# 1_Main__schdoc.net
KiCad netlist of a schematic drawn in Altium Designer
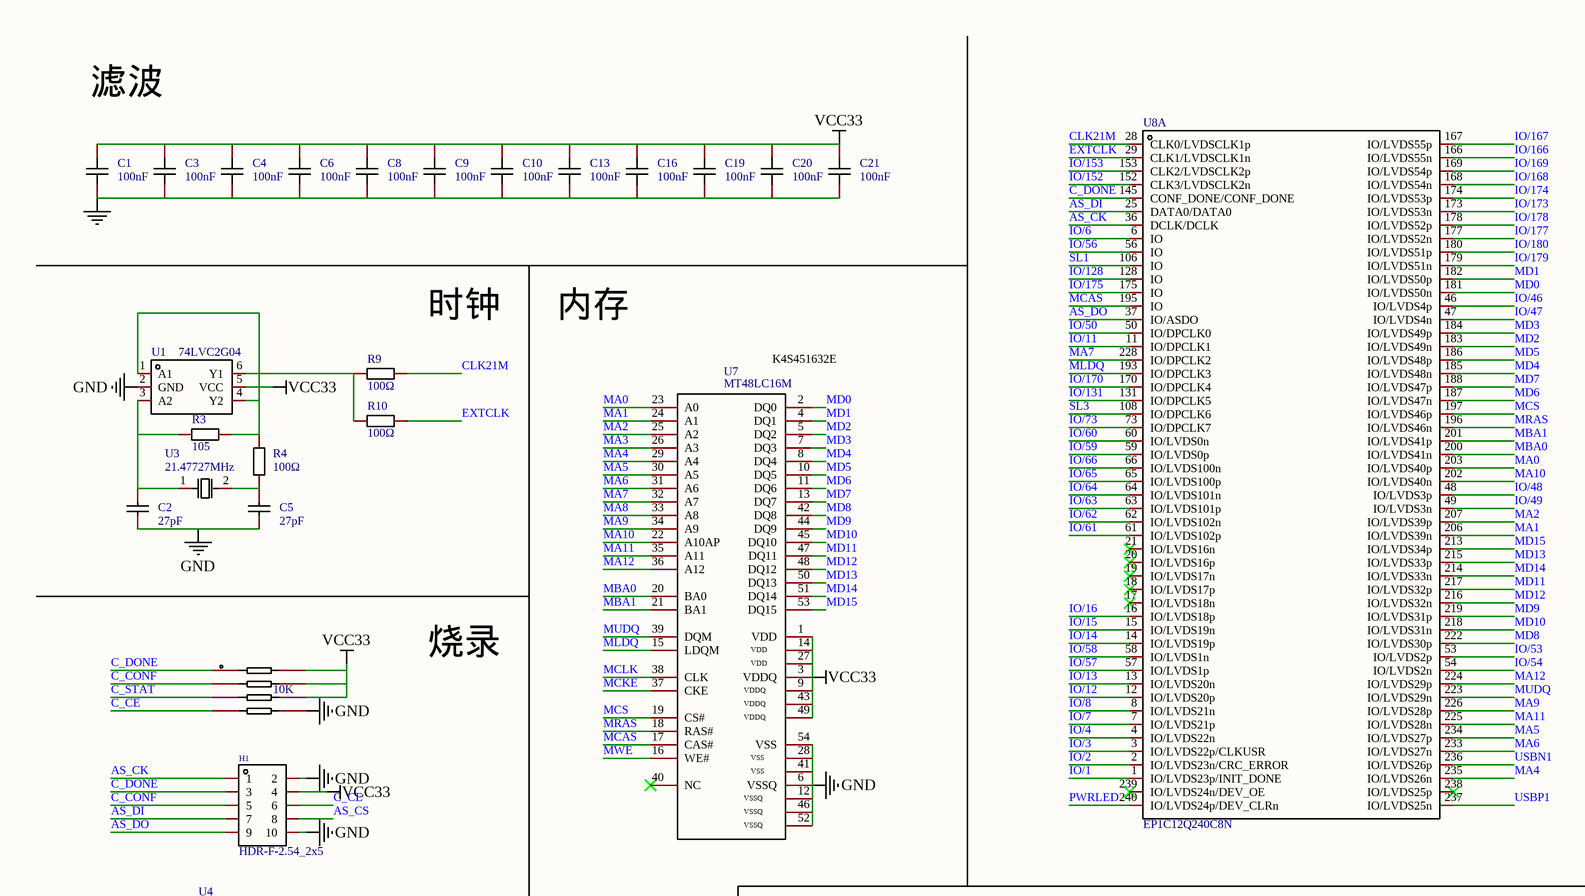
[diagram p0: 1_Main_核心板.schdoc.schdoc, top left]
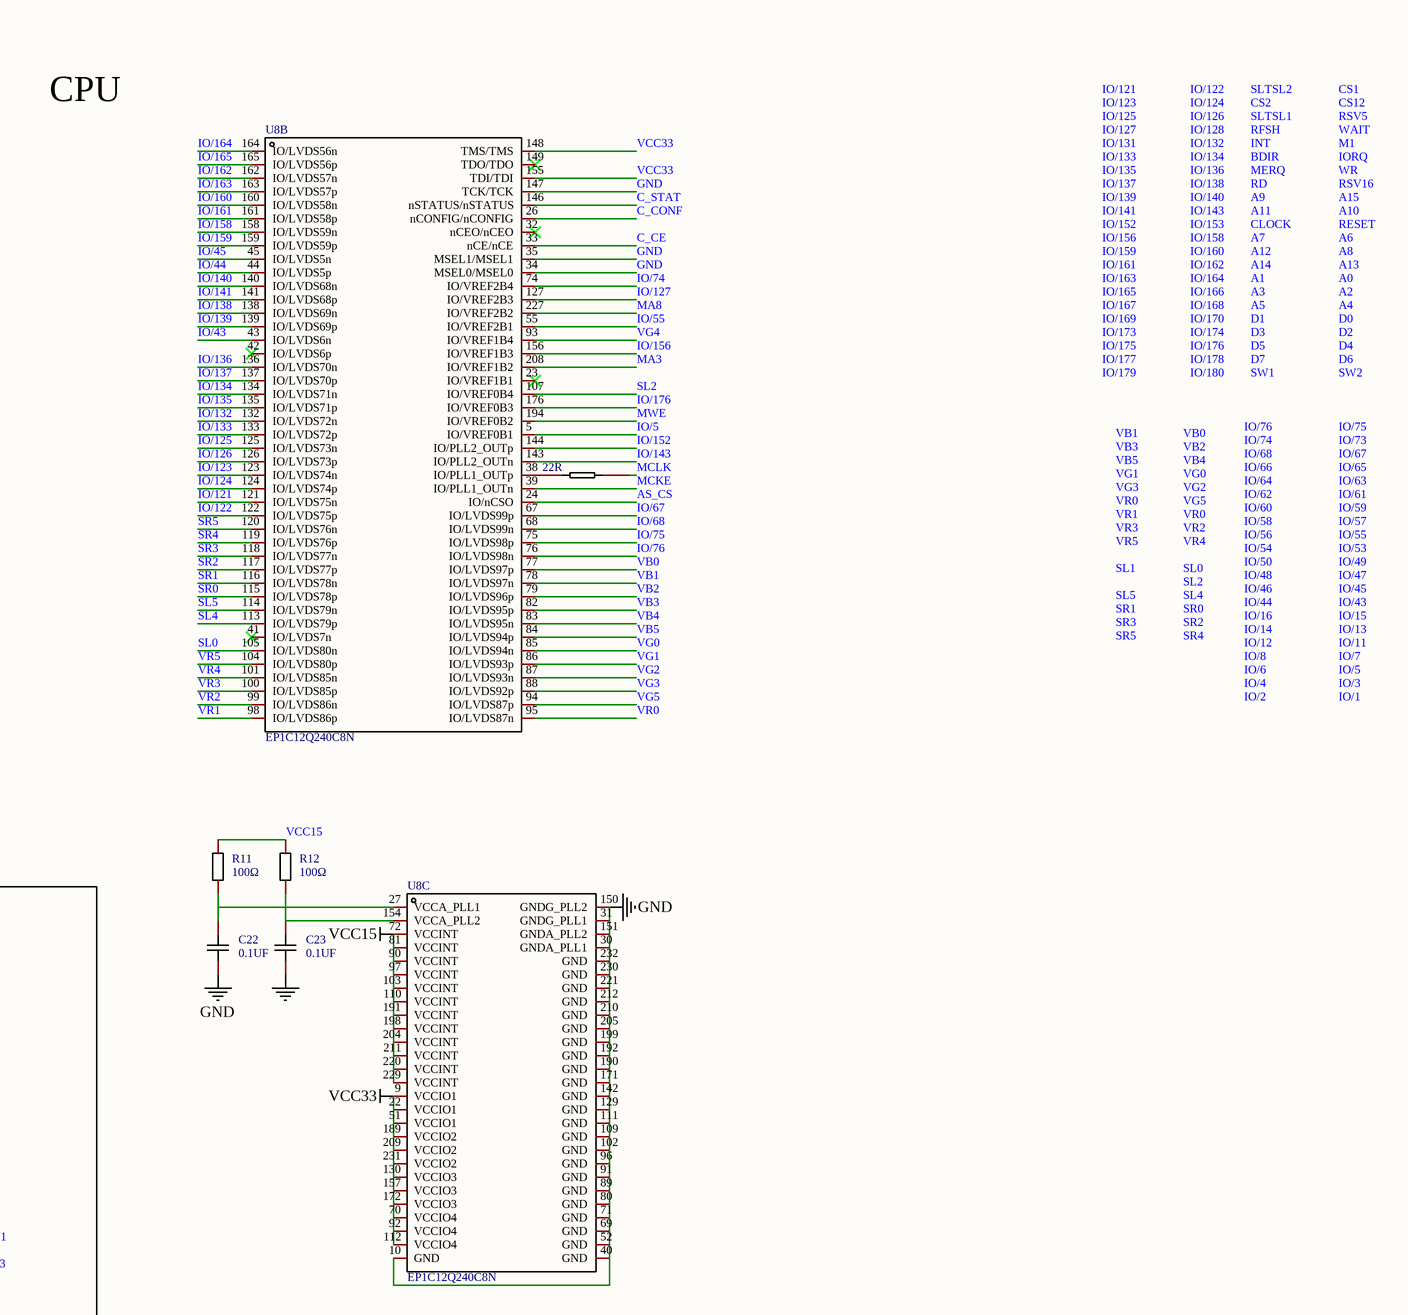
[diagram p1: 1_Main_核心板.schdoc.schdoc, top right]
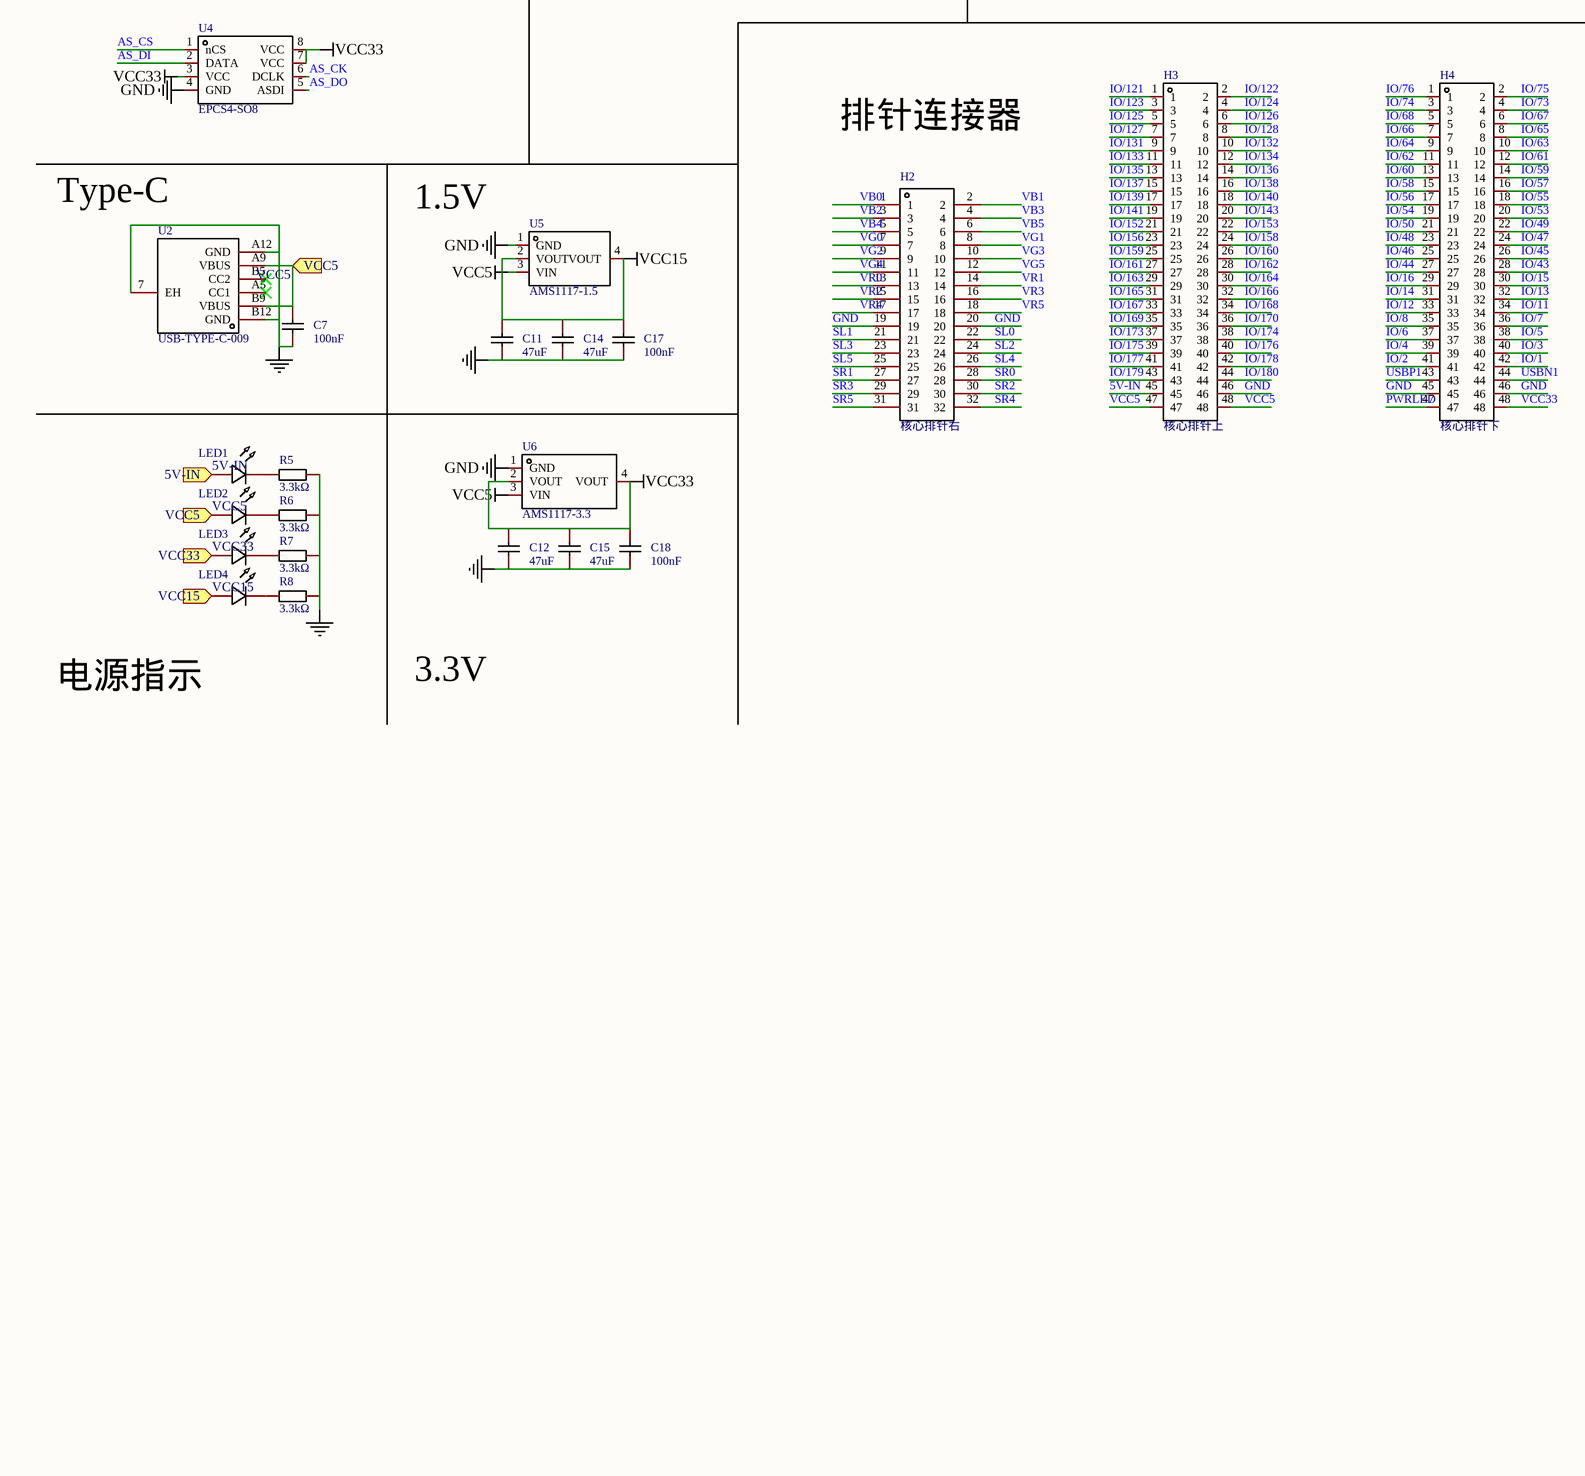
[diagram p2: 1_Main_核心板.schdoc.schdoc, bottom left]

(export (version "E")
  (design (tool "Eeschema 10.0.6"))
  (components
    (comp (ref "C1")
      (value "100nF")
      (fields
        (field (name "NAME") "100nF")
        (field (name "MANUFACTURER") "YAGEO(国巨)")
        (field (name "MANUFACTURER PART") "CC0603KRX7R9BB104")
        (field (name "TOLERANCE") "±10%")
      )
      (libsource (lib "altium-import") (part "root_1_CC0603KRX7R9BB104_"))
    )
    (comp (ref "C2")
      (value "27pF")
      (fields
        (field (name "NAME") "27pF")
        (field (name "MANUFACTURER") "YAGEO(国巨)")
        (field (name "MANUFACTURER PART") "CC0603JRNPO9BN270")
        (field (name "TOLERANCE") "±5%")
      )
      (libsource (lib "altium-import") (part "root_1_CC0603JRNPO9BN270_"))
    )
    (comp (ref "C3")
      (value "100nF")
      (fields
        (field (name "NAME") "100nF")
        (field (name "MANUFACTURER") "YAGEO(国巨)")
        (field (name "MANUFACTURER PART") "CC0603KRX7R9BB104")
        (field (name "TOLERANCE") "±10%")
      )
      (libsource (lib "altium-import") (part "root_1_CC0603KRX7R9BB104_"))
    )
    (comp (ref "C4")
      (value "100nF")
      (fields
        (field (name "NAME") "100nF")
        (field (name "MANUFACTURER") "YAGEO(国巨)")
        (field (name "MANUFACTURER PART") "CC0603KRX7R9BB104")
        (field (name "TOLERANCE") "±10%")
      )
      (libsource (lib "altium-import") (part "root_1_CC0603KRX7R9BB104_"))
    )
    (comp (ref "C5")
      (value "27pF")
      (fields
        (field (name "NAME") "27pF")
        (field (name "MANUFACTURER") "YAGEO(国巨)")
        (field (name "MANUFACTURER PART") "CC0603JRNPO9BN270")
        (field (name "TOLERANCE") "±5%")
      )
      (libsource (lib "altium-import") (part "root_1_CC0603JRNPO9BN270_"))
    )
    (comp (ref "C6")
      (value "100nF")
      (fields
        (field (name "NAME") "100nF")
        (field (name "MANUFACTURER") "YAGEO(国巨)")
        (field (name "MANUFACTURER PART") "CC0603KRX7R9BB104")
        (field (name "TOLERANCE") "±10%")
      )
      (libsource (lib "altium-import") (part "root_1_CC0603KRX7R9BB104_"))
    )
    (comp (ref "C7")
      (value "100nF")
      (fields
        (field (name "NAME") "100nF")
        (field (name "MANUFACTURER") "FH(风华)")
        (field (name "MANUFACTURER PART") "0603B104K500NT")
        (field (name "TOLERANCE") "±10%")
      )
      (libsource (lib "altium-import") (part "root_1_0603B104K500NT_"))
    )
    (comp (ref "C8")
      (value "100nF")
      (fields
        (field (name "NAME") "100nF")
        (field (name "MANUFACTURER") "YAGEO(国巨)")
        (field (name "MANUFACTURER PART") "CC0603KRX7R9BB104")
        (field (name "TOLERANCE") "±10%")
      )
      (libsource (lib "altium-import") (part "root_1_CC0603KRX7R9BB104_"))
    )
    (comp (ref "C9")
      (value "100nF")
      (fields
        (field (name "NAME") "100nF")
        (field (name "MANUFACTURER") "YAGEO(国巨)")
        (field (name "MANUFACTURER PART") "CC0603KRX7R9BB104")
        (field (name "TOLERANCE") "±10%")
      )
      (libsource (lib "altium-import") (part "root_1_CC0603KRX7R9BB104_"))
    )
    (comp (ref "C10")
      (value "100nF")
      (fields
        (field (name "NAME") "100nF")
        (field (name "MANUFACTURER") "YAGEO(国巨)")
        (field (name "MANUFACTURER PART") "CC0603KRX7R9BB104")
        (field (name "TOLERANCE") "±10%")
      )
      (libsource (lib "altium-import") (part "root_1_CC0603KRX7R9BB104_"))
    )
    (comp (ref "C11")
      (value "47uF")
      (fields
        (field (name "NAME") "47uF")
        (field (name "MANUFACTURER") "SAMSUNG(三星)")
        (field (name "MANUFACTURER PART") "CL21A476MQYNNNE")
        (field (name "TOLERANCE") "±20%")
      )
      (libsource (lib "altium-import") (part "root_1_CL21A476MQYNNNE_"))
    )
    (comp (ref "C12")
      (value "47uF")
      (fields
        (field (name "NAME") "47uF")
        (field (name "MANUFACTURER") "SAMSUNG(三星)")
        (field (name "MANUFACTURER PART") "CL21A476MQYNNNE")
        (field (name "TOLERANCE") "±20%")
      )
      (libsource (lib "altium-import") (part "root_1_CL21A476MQYNNNE_"))
    )
    (comp (ref "C13")
      (value "100nF")
      (fields
        (field (name "NAME") "100nF")
        (field (name "MANUFACTURER") "YAGEO(国巨)")
        (field (name "MANUFACTURER PART") "CC0603KRX7R9BB104")
        (field (name "TOLERANCE") "±10%")
      )
      (libsource (lib "altium-import") (part "root_1_CC0603KRX7R9BB104_"))
    )
    (comp (ref "C14")
      (value "47uF")
      (fields
        (field (name "NAME") "47uF")
        (field (name "MANUFACTURER") "SAMSUNG(三星)")
        (field (name "MANUFACTURER PART") "CL21A476MQYNNNE")
        (field (name "TOLERANCE") "±20%")
      )
      (libsource (lib "altium-import") (part "root_1_CL21A476MQYNNNE_"))
    )
    (comp (ref "C15")
      (value "47uF")
      (fields
        (field (name "NAME") "47uF")
        (field (name "MANUFACTURER") "SAMSUNG(三星)")
        (field (name "MANUFACTURER PART") "CL21A476MQYNNNE")
        (field (name "TOLERANCE") "±20%")
      )
      (libsource (lib "altium-import") (part "root_1_CL21A476MQYNNNE_"))
    )
    (comp (ref "C16")
      (value "100nF")
      (fields
        (field (name "NAME") "100nF")
        (field (name "MANUFACTURER") "YAGEO(国巨)")
        (field (name "MANUFACTURER PART") "CC0603KRX7R9BB104")
        (field (name "TOLERANCE") "±10%")
      )
      (libsource (lib "altium-import") (part "root_1_CC0603KRX7R9BB104_"))
    )
    (comp (ref "C17")
      (value "100nF")
      (fields
        (field (name "NAME") "100nF")
        (field (name "MANUFACTURER") "FH(风华)")
        (field (name "MANUFACTURER PART") "0603B104K500NT")
        (field (name "TOLERANCE") "±10%")
      )
      (libsource (lib "altium-import") (part "root_1_0603B104K500NT_"))
    )
    (comp (ref "C18")
      (value "100nF")
      (fields
        (field (name "NAME") "100nF")
        (field (name "MANUFACTURER") "FH(风华)")
        (field (name "MANUFACTURER PART") "0603B104K500NT")
        (field (name "TOLERANCE") "±10%")
      )
      (libsource (lib "altium-import") (part "root_1_0603B104K500NT_"))
    )
    (comp (ref "C19")
      (value "100nF")
      (fields
        (field (name "NAME") "100nF")
        (field (name "MANUFACTURER") "YAGEO(国巨)")
        (field (name "MANUFACTURER PART") "CC0603KRX7R9BB104")
        (field (name "TOLERANCE") "±10%")
      )
      (libsource (lib "altium-import") (part "root_1_CC0603KRX7R9BB104_"))
    )
    (comp (ref "C20")
      (value "100nF")
      (fields
        (field (name "NAME") "100nF")
        (field (name "MANUFACTURER") "YAGEO(国巨)")
        (field (name "MANUFACTURER PART") "CC0603KRX7R9BB104")
        (field (name "TOLERANCE") "±10%")
      )
      (libsource (lib "altium-import") (part "root_1_CC0603KRX7R9BB104_"))
    )
    (comp (ref "C21")
      (value "100nF")
      (fields
        (field (name "NAME") "100nF")
        (field (name "MANUFACTURER") "YAGEO(国巨)")
        (field (name "MANUFACTURER PART") "CC0603KRX7R9BB104")
        (field (name "TOLERANCE") "±10%")
      )
      (libsource (lib "altium-import") (part "root_1_CC0603KRX7R9BB104_"))
    )
    (comp (ref "C22")
      (value "0.1UF")
      (fields (field (name "NAME") "0.1UF"))
      (libsource (lib "altium-import") (part "root_3_0.1UF_"))
    )
    (comp (ref "C23")
      (value "0.1UF")
      (fields (field (name "NAME") "0.1UF"))
      (libsource (lib "altium-import") (part "root_3_mirrored_0.1UF_"))
    )
    (comp (ref "H1")
      (value "HDR-F-2.54_2x5")
      (description "排数:双排;总孔位数:10P;间距:2.54mm;行距:2.54mm;安装类型:直插;塑高:-;触头材质:黄铜;触头镀层:-;")
      (fields (field (name "NAME") "HDR-F-2.54_2x5") (field (name "MANUFACTURER") "BOOMELE(博穆精密)"))
      (libsource (lib "altium-import") (part "root_0_排母2.54mm2*5p 直_"))
    )
    (comp (ref "H2")
      (value "核心排针右")
      (fields (field (name "NAME") "核心排针右") (field (name "MANUFACTURER") "Ckmtw(灿科盟)"))
      (libsource (lib "altium-import") (part "root_0_B-2100S32P-B110_"))
    )
    (comp (ref "H3")
      (value "核心排针上")
      (fields (field (name "NAME") "核心排针上") (field (name "MANUFACTURER") "XKB Connectivity(中国星坤)"))
      (libsource (lib "altium-import") (part "root_0_X6521WV-2x24H-C60D30_"))
    )
    (comp (ref "H4")
      (value "核心排针下")
      (fields (field (name "NAME") "核心排针下") (field (name "MANUFACTURER") "XKB Connectivity(中国星坤)"))
      (libsource (lib "altium-import") (part "root_0_X6521WV-2x24H-C60D30_"))
    )
    (comp (ref "LED1") (value "LED_0603-R") (libsource (lib "altium-import") (part "root_0_LED_0603-R_")))
    (comp (ref "LED2") (value "LED_0603-R") (libsource (lib "altium-import") (part "root_0_LED_0603-R_")))
    (comp (ref "LED3") (value "LED_0603-R") (libsource (lib "altium-import") (part "root_0_LED_0603-R_")))
    (comp (ref "LED4") (value "LED_0603-R") (libsource (lib "altium-import") (part "root_0_LED_0603-R_")))
    (comp (ref "R3")
      (value "105")
      (fields
        (field (name "NAME") "105")
        (field (name "MANUFACTURER") "UNI-ROYAL(厚声)")
        (field (name "MANUFACTURER PART") "0603WAF1004T5E")
        (field (name "TOLERANCE") "±1%")
      )
      (libsource (lib "altium-import") (part "root_0_0603WAF1004T5E_"))
    )
    (comp (ref "R4")
      (value "100Ω")
      (fields
        (field (name "NAME") "100Ω")
        (field (name "MANUFACTURER") "UNI-ROYAL(厚声)")
        (field (name "MANUFACTURER PART") "0603WAF1000T5E")
        (field (name "TOLERANCE") "±1%")
      )
      (libsource (lib "altium-import") (part "root_1_0603WAF1000T5E_"))
    )
    (comp (ref "R5")
      (value "3.3kΩ")
      (fields
        (field (name "NAME") "3.3kΩ")
        (field (name "MANUFACTURER") "UNI-ROYAL(厚声)")
        (field (name "MANUFACTURER PART") "0603WAF3301T5E")
        (field (name "TOLERANCE") "±1%")
      )
      (libsource (lib "altium-import") (part "root_0_0603WAF3301T5E_"))
    )
    (comp (ref "R6")
      (value "3.3kΩ")
      (fields
        (field (name "NAME") "3.3kΩ")
        (field (name "MANUFACTURER") "UNI-ROYAL(厚声)")
        (field (name "MANUFACTURER PART") "0603WAF3301T5E")
        (field (name "TOLERANCE") "±1%")
      )
      (libsource (lib "altium-import") (part "root_0_0603WAF3301T5E_"))
    )
    (comp (ref "R7")
      (value "3.3kΩ")
      (fields
        (field (name "NAME") "3.3kΩ")
        (field (name "MANUFACTURER") "UNI-ROYAL(厚声)")
        (field (name "MANUFACTURER PART") "0603WAF3301T5E")
        (field (name "TOLERANCE") "±1%")
      )
      (libsource (lib "altium-import") (part "root_0_0603WAF3301T5E_"))
    )
    (comp (ref "R8")
      (value "3.3kΩ")
      (fields
        (field (name "NAME") "3.3kΩ")
        (field (name "MANUFACTURER") "UNI-ROYAL(厚声)")
        (field (name "MANUFACTURER PART") "0603WAF3301T5E")
        (field (name "TOLERANCE") "±1%")
      )
      (libsource (lib "altium-import") (part "root_0_0603WAF3301T5E_"))
    )
    (comp (ref "R9")
      (value "100Ω")
      (fields
        (field (name "NAME") "100Ω")
        (field (name "MANUFACTURER") "UNI-ROYAL(厚声)")
        (field (name "MANUFACTURER PART") "0603WAF1000T5E")
        (field (name "TOLERANCE") "±1%")
      )
      (libsource (lib "altium-import") (part "root_0_0603WAF1000T5E_"))
    )
    (comp (ref "R10")
      (value "100Ω")
      (fields
        (field (name "NAME") "100Ω")
        (field (name "MANUFACTURER") "UNI-ROYAL(厚声)")
        (field (name "MANUFACTURER PART") "0603WAF1000T5E")
        (field (name "TOLERANCE") "±1%")
      )
      (libsource (lib "altium-import") (part "root_0_0603WAF1000T5E_"))
    )
    (comp (ref "R11")
      (value "100Ω")
      (fields
        (field (name "NAME") "100Ω")
        (field (name "MANUFACTURER") "UNI-ROYAL(厚声)")
        (field (name "MANUFACTURER PART") "0603WAF1000T5E")
        (field (name "TOLERANCE") "±1%")
      )
      (libsource (lib "altium-import") (part "root_1_0603WAF1000T5E_"))
    )
    (comp (ref "R12")
      (value "100Ω")
      (fields
        (field (name "NAME") "100Ω")
        (field (name "MANUFACTURER") "UNI-ROYAL(厚声)")
        (field (name "MANUFACTURER PART") "0603WAF1000T5E")
        (field (name "TOLERANCE") "±1%")
      )
      (libsource (lib "altium-import") (part "root_1_0603WAF1000T5E_"))
    )
    (comp (ref "R13")
      (value "22R")
      (fields (field (name "NAME") "22R"))
      (libsource (lib "altium-import") (part "root_0_Res_0603_"))
    )
    (comp (ref "RN2")
      (value "10K")
      (fields
        (field (name "NAME") "10K")
        (field (name "MANUFACTURER") "UNI-ROYAL(厚声)")
        (field (name "MANUFACTURER PART") "4D03WGJ0101T5E")
        (field (name "TOLERANCE") "±5%")
      )
      (libsource (lib "altium-import") (part "root_0_4D03WGJ0101T5E_"))
    )
    (comp (ref "U1")
      (value "74LVC2G04")
      (description "输入类型:-;通道数:2;电源电压:1.8V~5.5V;电源电流(最大值):1uA;灌电流(IOL):8mA;拉电流(IOH):8mA;最大传播延迟(tpd):5.6ns@5V,50pF;")
      (fields (field (name "NAME") "74LVC2G04") (field (name "MANUFACTURER") "onsemi(安森美)"))
      (libsource (lib "altium-import") (part "root_0_NC7WZU04P6X_"))
    )
    (comp (ref "U2")
      (value "USB-TYPE-C-009")
      (description "连接器类型:Type-C;标准:-;公母:母座;触点数量:6;端口数量:1;安装方式:卧贴;额定电流 - 电源:5A;工作温度范围:-25℃~+85℃;")
      (fields (field (name "NAME") "USB-TYPE-C-009") (field (name "MANUFACTURER") "DEALON(德艺隆)"))
      (libsource (lib "altium-import") (part "root_2_USB-TYPE-C-009_"))
    )
    (comp (ref "U3")
      (value "21.47727MHz")
      (description "频率:21.47727MHz;频率公差:±30ppm;频率稳定度:±50ppm;负载电容:-;")
      (fields
        (field (name "NAME") "21.47727MHz")
        (field (name "MANUFACTURER") "ECS")
        (field (name "MANUFACTURER PART") "ECS-214.7-S-4")
      )
      (libsource (lib "altium-import") (part "root_0_ECS-214.7-S-4_"))
    )
    (comp (ref "U4")
      (value "EPCS4-SO8")
      (fields (field (name "NAME") "EPCS4-SO8"))
      (libsource (lib "altium-import") (part "root_0_EPCS4-SO8_"))
    )
    (comp (ref "U5")
      (value "AMS1117-1.5")
      (description "输出类型:-;")
      (fields (field (name "NAME") "AMS1117-1.5") (field (name "MANUFACTURER") "JSMSEMI(杰盛微)"))
      (libsource (lib "altium-import") (part "root_0_AMS1117-1.5_C963403_"))
    )
    (comp (ref "U6")
      (value "AMS1117-3.3")
      (description "输出类型:固定;输出极性:正;最大输入电压:-;输出电压:3.3V;输出电流:1A;电源纹波抑制比(PSRR):72dB@(120Hz);")
      (fields (field (name "NAME") "AMS1117-3.3") (field (name "MANUFACTURER") "AMS"))
      (libsource (lib "altium-import") (part "root_0_AMS1117-3.3_C6186_"))
    )
    (comp (ref "U7")
      (value "MT48LC16M")
      (fields (field (name "NAME") "MT48LC16M"))
      (libsource (lib "altium-import") (part "root_0_MT48LC16M_"))
    )
    (comp (ref "U8")
      (value "EP1C12Q240C8N")
      (fields (field (name "NAME") "EP1C12Q240C8N") (field (name "MANUFACTURER") "Intel/Altera"))
      (libsource (lib "altium-import") (part "root_0_EP1C12Q240C8N_"))
    )
  )
  (nets
    (net (code "1") (name "/5V-IN") (class "Default")
      (node (ref "H3") (pin "45") (pinfunction "45_45") (pintype "passive"))
      (node (ref "LED1") (pin "2") (pinfunction "A_2") (pintype "passive"))
    )
    (net (code "18") (name "/AS_CK") (class "Default")
      (node (ref "H1") (pin "1") (pinfunction "1_1") (pintype "passive"))
      (node (ref "U4") (pin "6") (pinfunction "DCLK_6") (pintype "passive"))
      (node (ref "U8") (pin "36") (pinfunction "DCLK/DCLK_36") (pintype "passive"))
    )
    (net (code "19") (name "/AS_CS") (class "Default")
      (node (ref "H1") (pin "8") (pinfunction "8_8") (pintype "passive"))
      (node (ref "U4") (pin "1") (pinfunction "nCS_1") (pintype "passive"))
      (node (ref "U8") (pin "24") (pinfunction "IO/nCSO_24") (pintype "passive"))
    )
    (net (code "20") (name "/AS_DI") (class "Default")
      (node (ref "H1") (pin "7") (pinfunction "7_7") (pintype "passive"))
      (node (ref "U4") (pin "2") (pinfunction "DATA_2") (pintype "passive"))
      (node (ref "U8") (pin "25") (pinfunction "DATA0/DATA0_25") (pintype "passive"))
    )
    (net (code "21") (name "/AS_DO") (class "Default")
      (node (ref "H1") (pin "9") (pinfunction "9_9") (pintype "passive"))
      (node (ref "U4") (pin "5") (pinfunction "ASDI_5") (pintype "passive"))
      (node (ref "U8") (pin "37") (pinfunction "IO/ASDO_37") (pintype "passive"))
    )
    (net (code "23") (name "/CLK21M") (class "Default")
      (node (ref "R9") (pin "2") (pinfunction "2_2") (pintype "passive"))
      (node (ref "U8") (pin "28") (pinfunction "CLK0/LVDSCLK1p_28") (pintype "passive"))
    )
    (net (code "28") (name "/C_CE") (class "Default")
      (node (ref "H1") (pin "6") (pinfunction "6_6") (pintype "passive"))
      (node (ref "RN2") (pin "4") (pinfunction "4_4") (pintype "passive"))
      (node (ref "U8") (pin "33") (pinfunction "nCE/nCE_33") (pintype "passive"))
    )
    (net (code "29") (name "/C_CONF") (class "Default")
      (node (ref "H1") (pin "5") (pinfunction "5_5") (pintype "passive"))
      (node (ref "RN2") (pin "2") (pinfunction "2_2") (pintype "passive"))
      (node (ref "U8") (pin "26") (pinfunction "nCONFIG/nCONFIG_26") (pintype "passive"))
    )
    (net (code "30") (name "/C_DONE") (class "Default")
      (node (ref "H1") (pin "3") (pinfunction "3_3") (pintype "passive"))
      (node (ref "RN2") (pin "1") (pinfunction "1_1") (pintype "passive"))
      (node (ref "U8") (pin "145") (pinfunction "CONF_DONE/CONF_DONE_145") (pintype "passive"))
    )
    (net (code "31") (name "/C_STAT") (class "Default")
      (node (ref "RN2") (pin "3") (pinfunction "3_3") (pintype "passive"))
      (node (ref "U8") (pin "146") (pinfunction "nSTATUS/nSTATUS_146") (pintype "passive"))
    )
    (net (code "40") (name "/EXTCLK") (class "Default")
      (node (ref "R10") (pin "2") (pinfunction "2_2") (pintype "passive"))
      (node (ref "U8") (pin "29") (pinfunction "CLK1/LVDSCLK1n_29") (pintype "passive"))
    )
    (net (code "43") (name "/IO{slash}1") (class "Default")
      (node (ref "H4") (pin "42") (pinfunction "42_42") (pintype "passive"))
      (node (ref "U8") (pin "1") (pinfunction "IO/LVDS23p/INIT_DONE_1") (pintype "passive"))
    )
    (net (code "44") (name "/IO{slash}2") (class "Default")
      (node (ref "H4") (pin "41") (pinfunction "41_41") (pintype "passive"))
      (node (ref "U8") (pin "2") (pinfunction "IO/LVDS23n/CRC_ERROR_2") (pintype "passive"))
    )
    (net (code "45") (name "/IO{slash}3") (class "Default")
      (node (ref "H4") (pin "40") (pinfunction "40_40") (pintype "passive"))
      (node (ref "U8") (pin "3") (pinfunction "IO/LVDS22p/CLKUSR_3") (pintype "passive"))
    )
    (net (code "46") (name "/IO{slash}4") (class "Default")
      (node (ref "H4") (pin "39") (pinfunction "39_39") (pintype "passive"))
      (node (ref "U8") (pin "4") (pinfunction "IO/LVDS22n_4") (pintype "passive"))
    )
    (net (code "47") (name "/IO{slash}5") (class "Default")
      (node (ref "H4") (pin "38") (pinfunction "38_38") (pintype "passive"))
      (node (ref "U8") (pin "5") (pinfunction "IO/VREF0B1_5") (pintype "passive"))
    )
    (net (code "48") (name "/IO{slash}6") (class "Default")
      (node (ref "H4") (pin "37") (pinfunction "37_37") (pintype "passive"))
      (node (ref "U8") (pin "6") (pinfunction "IO_6") (pintype "passive"))
    )
    (net (code "49") (name "/IO{slash}7") (class "Default")
      (node (ref "H4") (pin "36") (pinfunction "36_36") (pintype "passive"))
      (node (ref "U8") (pin "7") (pinfunction "IO/LVDS21p_7") (pintype "passive"))
    )
    (net (code "50") (name "/IO{slash}8") (class "Default")
      (node (ref "H4") (pin "35") (pinfunction "35_35") (pintype "passive"))
      (node (ref "U8") (pin "8") (pinfunction "IO/LVDS21n_8") (pintype "passive"))
    )
    (net (code "51") (name "/IO{slash}11") (class "Default")
      (node (ref "H4") (pin "34") (pinfunction "34_34") (pintype "passive"))
      (node (ref "U8") (pin "11") (pinfunction "IO/DPCLK1_11") (pintype "passive"))
    )
    (net (code "52") (name "/IO{slash}12") (class "Default")
      (node (ref "H4") (pin "33") (pinfunction "33_33") (pintype "passive"))
      (node (ref "U8") (pin "12") (pinfunction "IO/LVDS20p_12") (pintype "passive"))
    )
    (net (code "53") (name "/IO{slash}13") (class "Default")
      (node (ref "H4") (pin "32") (pinfunction "32_32") (pintype "passive"))
      (node (ref "U8") (pin "13") (pinfunction "IO/LVDS20n_13") (pintype "passive"))
    )
    (net (code "54") (name "/IO{slash}14") (class "Default")
      (node (ref "H4") (pin "31") (pinfunction "31_31") (pintype "passive"))
      (node (ref "U8") (pin "14") (pinfunction "IO/LVDS19p_14") (pintype "passive"))
    )
    (net (code "55") (name "/IO{slash}15") (class "Default")
      (node (ref "H4") (pin "30") (pinfunction "30_30") (pintype "passive"))
      (node (ref "U8") (pin "15") (pinfunction "IO/LVDS19n_15") (pintype "passive"))
    )
    (net (code "56") (name "/IO{slash}16") (class "Default")
      (node (ref "H4") (pin "29") (pinfunction "29_29") (pintype "passive"))
      (node (ref "U8") (pin "16") (pinfunction "IO/LVDS18p_16") (pintype "passive"))
    )
    (net (code "57") (name "/IO{slash}43") (class "Default")
      (node (ref "H4") (pin "28") (pinfunction "28_28") (pintype "passive"))
      (node (ref "U8") (pin "43") (pinfunction "IO/LVDS6n_43") (pintype "passive"))
    )
    (net (code "58") (name "/IO{slash}44") (class "Default")
      (node (ref "H4") (pin "27") (pinfunction "27_27") (pintype "passive"))
      (node (ref "U8") (pin "44") (pinfunction "IO/LVDS5p_44") (pintype "passive"))
    )
    (net (code "59") (name "/IO{slash}45") (class "Default")
      (node (ref "H4") (pin "26") (pinfunction "26_26") (pintype "passive"))
      (node (ref "U8") (pin "45") (pinfunction "IO/LVDS5n_45") (pintype "passive"))
    )
    (net (code "60") (name "/IO{slash}46") (class "Default")
      (node (ref "H4") (pin "25") (pinfunction "25_25") (pintype "passive"))
      (node (ref "U8") (pin "46") (pinfunction "IO/LVDS4p_46") (pintype "passive"))
    )
    (net (code "61") (name "/IO{slash}47") (class "Default")
      (node (ref "H4") (pin "24") (pinfunction "24_24") (pintype "passive"))
      (node (ref "U8") (pin "47") (pinfunction "IO/LVDS4n_47") (pintype "passive"))
    )
    (net (code "62") (name "/IO{slash}48") (class "Default")
      (node (ref "H4") (pin "23") (pinfunction "23_23") (pintype "passive"))
      (node (ref "U8") (pin "48") (pinfunction "IO/LVDS3p_48") (pintype "passive"))
    )
    (net (code "63") (name "/IO{slash}49") (class "Default")
      (node (ref "H4") (pin "22") (pinfunction "22_22") (pintype "passive"))
      (node (ref "U8") (pin "49") (pinfunction "IO/LVDS3n_49") (pintype "passive"))
    )
    (net (code "64") (name "/IO{slash}50") (class "Default")
      (node (ref "H4") (pin "21") (pinfunction "21_21") (pintype "passive"))
      (node (ref "U8") (pin "50") (pinfunction "IO/DPCLK0_50") (pintype "passive"))
    )
    (net (code "65") (name "/IO{slash}53") (class "Default")
      (node (ref "H4") (pin "20") (pinfunction "20_20") (pintype "passive"))
      (node (ref "U8") (pin "53") (pinfunction "IO/LVDS2p_53") (pintype "passive"))
    )
    (net (code "66") (name "/IO{slash}54") (class "Default")
      (node (ref "H4") (pin "19") (pinfunction "19_19") (pintype "passive"))
      (node (ref "U8") (pin "54") (pinfunction "IO/LVDS2n_54") (pintype "passive"))
    )
    (net (code "67") (name "/IO{slash}55") (class "Default")
      (node (ref "H4") (pin "18") (pinfunction "18_18") (pintype "passive"))
      (node (ref "U8") (pin "55") (pinfunction "IO/VREF2B1_55") (pintype "passive"))
    )
    (net (code "68") (name "/IO{slash}56") (class "Default")
      (node (ref "H4") (pin "17") (pinfunction "17_17") (pintype "passive"))
      (node (ref "U8") (pin "56") (pinfunction "IO_56") (pintype "passive"))
    )
    (net (code "69") (name "/IO{slash}57") (class "Default")
      (node (ref "H4") (pin "16") (pinfunction "16_16") (pintype "passive"))
      (node (ref "U8") (pin "57") (pinfunction "IO/LVDS1p_57") (pintype "passive"))
    )
    (net (code "70") (name "/IO{slash}58") (class "Default")
      (node (ref "H4") (pin "15") (pinfunction "15_15") (pintype "passive"))
      (node (ref "U8") (pin "58") (pinfunction "IO/LVDS1n_58") (pintype "passive"))
    )
    (net (code "71") (name "/IO{slash}59") (class "Default")
      (node (ref "H4") (pin "14") (pinfunction "14_14") (pintype "passive"))
      (node (ref "U8") (pin "59") (pinfunction "IO/LVDS0p_59") (pintype "passive"))
    )
    (net (code "72") (name "/IO{slash}60") (class "Default")
      (node (ref "H4") (pin "13") (pinfunction "13_13") (pintype "passive"))
      (node (ref "U8") (pin "60") (pinfunction "IO/LVDS0n_60") (pintype "passive"))
    )
    (net (code "73") (name "/IO{slash}61") (class "Default")
      (node (ref "H4") (pin "12") (pinfunction "12_12") (pintype "passive"))
      (node (ref "U8") (pin "61") (pinfunction "IO/LVDS102p_61") (pintype "passive"))
    )
    (net (code "74") (name "/IO{slash}62") (class "Default")
      (node (ref "H4") (pin "11") (pinfunction "11_11") (pintype "passive"))
      (node (ref "U8") (pin "62") (pinfunction "IO/LVDS102n_62") (pintype "passive"))
    )
    (net (code "75") (name "/IO{slash}63") (class "Default")
      (node (ref "H4") (pin "10") (pinfunction "10_10") (pintype "passive"))
      (node (ref "U8") (pin "63") (pinfunction "IO/LVDS101p_63") (pintype "passive"))
    )
    (net (code "76") (name "/IO{slash}64") (class "Default")
      (node (ref "H4") (pin "9") (pinfunction "9_9") (pintype "passive"))
      (node (ref "U8") (pin "64") (pinfunction "IO/LVDS101n_64") (pintype "passive"))
    )
    (net (code "77") (name "/IO{slash}65") (class "Default")
      (node (ref "H4") (pin "8") (pinfunction "8_8") (pintype "passive"))
      (node (ref "U8") (pin "65") (pinfunction "IO/LVDS100p_65") (pintype "passive"))
    )
    (net (code "78") (name "/IO{slash}66") (class "Default")
      (node (ref "H4") (pin "7") (pinfunction "7_7") (pintype "passive"))
      (node (ref "U8") (pin "66") (pinfunction "IO/LVDS100n_66") (pintype "passive"))
    )
    (net (code "79") (name "/IO{slash}67") (class "Default")
      (node (ref "H4") (pin "6") (pinfunction "6_6") (pintype "passive"))
      (node (ref "U8") (pin "67") (pinfunction "IO/LVDS99p_67") (pintype "passive"))
    )
    (net (code "80") (name "/IO{slash}68") (class "Default")
      (node (ref "H4") (pin "5") (pinfunction "5_5") (pintype "passive"))
      (node (ref "U8") (pin "68") (pinfunction "IO/LVDS99n_68") (pintype "passive"))
    )
    (net (code "81") (name "/IO{slash}73") (class "Default")
      (node (ref "H4") (pin "4") (pinfunction "4_4") (pintype "passive"))
      (node (ref "U8") (pin "73") (pinfunction "IO/DPCLK7_73") (pintype "passive"))
    )
    (net (code "82") (name "/IO{slash}74") (class "Default")
      (node (ref "H4") (pin "3") (pinfunction "3_3") (pintype "passive"))
      (node (ref "U8") (pin "74") (pinfunction "IO/VREF2B4_74") (pintype "passive"))
    )
    (net (code "83") (name "/IO{slash}75") (class "Default")
      (node (ref "H4") (pin "2") (pinfunction "2_2") (pintype "passive"))
      (node (ref "U8") (pin "75") (pinfunction "IO/LVDS98p_75") (pintype "passive"))
    )
    (net (code "84") (name "/IO{slash}76") (class "Default")
      (node (ref "H4") (pin "1") (pinfunction "1_1") (pintype "passive"))
      (node (ref "U8") (pin "76") (pinfunction "IO/LVDS98n_76") (pintype "passive"))
    )
    (net (code "85") (name "/IO{slash}121") (class "Default")
      (node (ref "H3") (pin "1") (pinfunction "1_1") (pintype "passive"))
      (node (ref "U8") (pin "121") (pinfunction "IO/LVDS75n_121") (pintype "passive"))
    )
    (net (code "86") (name "/IO{slash}122") (class "Default")
      (node (ref "H3") (pin "2") (pinfunction "2_2") (pintype "passive"))
      (node (ref "U8") (pin "122") (pinfunction "IO/LVDS75p_122") (pintype "passive"))
    )
    (net (code "87") (name "/IO{slash}123") (class "Default")
      (node (ref "H3") (pin "3") (pinfunction "3_3") (pintype "passive"))
      (node (ref "U8") (pin "123") (pinfunction "IO/LVDS74n_123") (pintype "passive"))
    )
    (net (code "88") (name "/IO{slash}124") (class "Default")
      (node (ref "H3") (pin "4") (pinfunction "4_4") (pintype "passive"))
      (node (ref "U8") (pin "124") (pinfunction "IO/LVDS74p_124") (pintype "passive"))
    )
    (net (code "89") (name "/IO{slash}125") (class "Default")
      (node (ref "H3") (pin "5") (pinfunction "5_5") (pintype "passive"))
      (node (ref "U8") (pin "125") (pinfunction "IO/LVDS73n_125") (pintype "passive"))
    )
    (net (code "90") (name "/IO{slash}126") (class "Default")
      (node (ref "H3") (pin "6") (pinfunction "6_6") (pintype "passive"))
      (node (ref "U8") (pin "126") (pinfunction "IO/LVDS73p_126") (pintype "passive"))
    )
    (net (code "91") (name "/IO{slash}127") (class "Default")
      (node (ref "H3") (pin "7") (pinfunction "7_7") (pintype "passive"))
      (node (ref "U8") (pin "127") (pinfunction "IO/VREF2B3_127") (pintype "passive"))
    )
    (net (code "92") (name "/IO{slash}128") (class "Default")
      (node (ref "H3") (pin "8") (pinfunction "8_8") (pintype "passive"))
      (node (ref "U8") (pin "128") (pinfunction "IO_128") (pintype "passive"))
    )
    (net (code "93") (name "/IO{slash}131") (class "Default")
      (node (ref "H3") (pin "9") (pinfunction "9_9") (pintype "passive"))
      (node (ref "U8") (pin "131") (pinfunction "IO/DPCLK5_131") (pintype "passive"))
    )
    (net (code "94") (name "/IO{slash}132") (class "Default")
      (node (ref "H3") (pin "10") (pinfunction "10_10") (pintype "passive"))
      (node (ref "U8") (pin "132") (pinfunction "IO/LVDS72n_132") (pintype "passive"))
    )
    (net (code "95") (name "/IO{slash}133") (class "Default")
      (node (ref "H3") (pin "11") (pinfunction "11_11") (pintype "passive"))
      (node (ref "U8") (pin "133") (pinfunction "IO/LVDS72p_133") (pintype "passive"))
    )
    (net (code "96") (name "/IO{slash}134") (class "Default")
      (node (ref "H3") (pin "12") (pinfunction "12_12") (pintype "passive"))
      (node (ref "U8") (pin "134") (pinfunction "IO/LVDS71n_134") (pintype "passive"))
    )
    (net (code "97") (name "/IO{slash}135") (class "Default")
      (node (ref "H3") (pin "13") (pinfunction "13_13") (pintype "passive"))
      (node (ref "U8") (pin "135") (pinfunction "IO/LVDS71p_135") (pintype "passive"))
    )
    (net (code "98") (name "/IO{slash}136") (class "Default")
      (node (ref "H3") (pin "14") (pinfunction "14_14") (pintype "passive"))
      (node (ref "U8") (pin "136") (pinfunction "IO/LVDS70n_136") (pintype "passive"))
    )
    (net (code "99") (name "/IO{slash}137") (class "Default")
      (node (ref "H3") (pin "15") (pinfunction "15_15") (pintype "passive"))
      (node (ref "U8") (pin "137") (pinfunction "IO/LVDS70p_137") (pintype "passive"))
    )
    (net (code "100") (name "/IO{slash}138") (class "Default")
      (node (ref "H3") (pin "16") (pinfunction "16_16") (pintype "passive"))
      (node (ref "U8") (pin "138") (pinfunction "IO/LVDS69n_138") (pintype "passive"))
    )
    (net (code "101") (name "/IO{slash}139") (class "Default")
      (node (ref "H3") (pin "17") (pinfunction "17_17") (pintype "passive"))
      (node (ref "U8") (pin "139") (pinfunction "IO/LVDS69p_139") (pintype "passive"))
    )
    (net (code "102") (name "/IO{slash}140") (class "Default")
      (node (ref "H3") (pin "18") (pinfunction "18_18") (pintype "passive"))
      (node (ref "U8") (pin "140") (pinfunction "IO/LVDS68n_140") (pintype "passive"))
    )
    (net (code "103") (name "/IO{slash}141") (class "Default")
      (node (ref "H3") (pin "19") (pinfunction "19_19") (pintype "passive"))
      (node (ref "U8") (pin "141") (pinfunction "IO/LVDS68p_141") (pintype "passive"))
    )
    (net (code "104") (name "/IO{slash}143") (class "Default")
      (node (ref "H3") (pin "20") (pinfunction "20_20") (pintype "passive"))
      (node (ref "U8") (pin "143") (pinfunction "IO/PLL2_OUTn_143") (pintype "passive"))
    )
    (net (code "105") (name "/IO{slash}152") (class "Default")
      (node (ref "H3") (pin "21") (pinfunction "21_21") (pintype "passive"))
      (node (ref "U8") (pin "144") (pinfunction "IO/PLL2_OUTp_144") (pintype "passive"))
      (node (ref "U8") (pin "152") (pinfunction "CLK3/LVDSCLK2n_152") (pintype "passive"))
    )
    (net (code "106") (name "/IO{slash}153") (class "Default")
      (node (ref "H3") (pin "22") (pinfunction "22_22") (pintype "passive"))
      (node (ref "U8") (pin "153") (pinfunction "CLK2/LVDSCLK2p_153") (pintype "passive"))
    )
    (net (code "107") (name "/IO{slash}156") (class "Default")
      (node (ref "H3") (pin "23") (pinfunction "23_23") (pintype "passive"))
      (node (ref "U8") (pin "156") (pinfunction "IO/VREF1B3_156") (pintype "passive"))
    )
    (net (code "108") (name "/IO{slash}158") (class "Default")
      (node (ref "H3") (pin "24") (pinfunction "24_24") (pintype "passive"))
      (node (ref "U8") (pin "158") (pinfunction "IO/LVDS59n_158") (pintype "passive"))
    )
    (net (code "109") (name "/IO{slash}159") (class "Default")
      (node (ref "H3") (pin "25") (pinfunction "25_25") (pintype "passive"))
      (node (ref "U8") (pin "159") (pinfunction "IO/LVDS59p_159") (pintype "passive"))
    )
    (net (code "110") (name "/IO{slash}160") (class "Default")
      (node (ref "H3") (pin "26") (pinfunction "26_26") (pintype "passive"))
      (node (ref "U8") (pin "160") (pinfunction "IO/LVDS58n_160") (pintype "passive"))
    )
    (net (code "111") (name "/IO{slash}161") (class "Default")
      (node (ref "H3") (pin "27") (pinfunction "27_27") (pintype "passive"))
      (node (ref "U8") (pin "161") (pinfunction "IO/LVDS58p_161") (pintype "passive"))
    )
    (net (code "112") (name "/IO{slash}162") (class "Default")
      (node (ref "H3") (pin "28") (pinfunction "28_28") (pintype "passive"))
      (node (ref "U8") (pin "162") (pinfunction "IO/LVDS57n_162") (pintype "passive"))
    )
    (net (code "113") (name "/IO{slash}163") (class "Default")
      (node (ref "H3") (pin "29") (pinfunction "29_29") (pintype "passive"))
      (node (ref "U8") (pin "163") (pinfunction "IO/LVDS57p_163") (pintype "passive"))
    )
    (net (code "114") (name "/IO{slash}164") (class "Default")
      (node (ref "H3") (pin "30") (pinfunction "30_30") (pintype "passive"))
      (node (ref "U8") (pin "164") (pinfunction "IO/LVDS56n_164") (pintype "passive"))
    )
    (net (code "115") (name "/IO{slash}165") (class "Default")
      (node (ref "H3") (pin "31") (pinfunction "31_31") (pintype "passive"))
      (node (ref "U8") (pin "165") (pinfunction "IO/LVDS56p_165") (pintype "passive"))
    )
    (net (code "116") (name "/IO{slash}166") (class "Default")
      (node (ref "H3") (pin "32") (pinfunction "32_32") (pintype "passive"))
      (node (ref "U8") (pin "166") (pinfunction "IO/LVDS55n_166") (pintype "passive"))
    )
    (net (code "117") (name "/IO{slash}167") (class "Default")
      (node (ref "H3") (pin "33") (pinfunction "33_33") (pintype "passive"))
      (node (ref "U8") (pin "167") (pinfunction "IO/LVDS55p_167") (pintype "passive"))
    )
    (net (code "118") (name "/IO{slash}168") (class "Default")
      (node (ref "H3") (pin "34") (pinfunction "34_34") (pintype "passive"))
      (node (ref "U8") (pin "168") (pinfunction "IO/LVDS54n_168") (pintype "passive"))
    )
    (net (code "119") (name "/IO{slash}169") (class "Default")
      (node (ref "H3") (pin "35") (pinfunction "35_35") (pintype "passive"))
      (node (ref "U8") (pin "169") (pinfunction "IO/LVDS54p_169") (pintype "passive"))
    )
    (net (code "120") (name "/IO{slash}170") (class "Default")
      (node (ref "H3") (pin "36") (pinfunction "36_36") (pintype "passive"))
      (node (ref "U8") (pin "170") (pinfunction "IO/DPCLK4_170") (pintype "passive"))
    )
    (net (code "121") (name "/IO{slash}173") (class "Default")
      (node (ref "H3") (pin "37") (pinfunction "37_37") (pintype "passive"))
      (node (ref "U8") (pin "173") (pinfunction "IO/LVDS53n_173") (pintype "passive"))
    )
    (net (code "122") (name "/IO{slash}174") (class "Default")
      (node (ref "H3") (pin "38") (pinfunction "38_38") (pintype "passive"))
      (node (ref "U8") (pin "174") (pinfunction "IO/LVDS53p_174") (pintype "passive"))
    )
    (net (code "123") (name "/IO{slash}175") (class "Default")
      (node (ref "H3") (pin "39") (pinfunction "39_39") (pintype "passive"))
      (node (ref "U8") (pin "175") (pinfunction "IO_175") (pintype "passive"))
    )
    (net (code "124") (name "/IO{slash}176") (class "Default")
      (node (ref "H3") (pin "40") (pinfunction "40_40") (pintype "passive"))
      (node (ref "U8") (pin "176") (pinfunction "IO/VREF0B3_176") (pintype "passive"))
    )
    (net (code "125") (name "/IO{slash}177") (class "Default")
      (node (ref "H3") (pin "41") (pinfunction "41_41") (pintype "passive"))
      (node (ref "U8") (pin "177") (pinfunction "IO/LVDS52n_177") (pintype "passive"))
    )
    (net (code "126") (name "/IO{slash}178") (class "Default")
      (node (ref "H3") (pin "42") (pinfunction "42_42") (pintype "passive"))
      (node (ref "U8") (pin "178") (pinfunction "IO/LVDS52p_178") (pintype "passive"))
    )
    (net (code "127") (name "/IO{slash}179") (class "Default")
      (node (ref "H3") (pin "43") (pinfunction "43_43") (pintype "passive"))
      (node (ref "U8") (pin "179") (pinfunction "IO/LVDS51n_179") (pintype "passive"))
    )
    (net (code "128") (name "/IO{slash}180") (class "Default")
      (node (ref "H3") (pin "44") (pinfunction "44_44") (pintype "passive"))
      (node (ref "U8") (pin "180") (pinfunction "IO/LVDS51p_180") (pintype "passive"))
    )
    (net (code "130") (name "/MA0") (class "Default")
      (node (ref "U7") (pin "23") (pinfunction "A0_23") (pintype "passive"))
      (node (ref "U8") (pin "203") (pinfunction "IO/LVDS40p_203") (pintype "passive"))
    )
    (net (code "131") (name "/MA1") (class "Default")
      (node (ref "U7") (pin "24") (pinfunction "A1_24") (pintype "passive"))
      (node (ref "U8") (pin "206") (pinfunction "IO/LVDS39n_206") (pintype "passive"))
    )
    (net (code "132") (name "/MA2") (class "Default")
      (node (ref "U7") (pin "25") (pinfunction "A2_25") (pintype "passive"))
      (node (ref "U8") (pin "207") (pinfunction "IO/LVDS39p_207") (pintype "passive"))
    )
    (net (code "133") (name "/MA3") (class "Default")
      (node (ref "U7") (pin "26") (pinfunction "A3_26") (pintype "passive"))
      (node (ref "U8") (pin "208") (pinfunction "IO/VREF1B2_208") (pintype "passive"))
    )
    (net (code "134") (name "/MA4") (class "Default")
      (node (ref "U7") (pin "29") (pinfunction "A4_29") (pintype "passive"))
      (node (ref "U8") (pin "235") (pinfunction "IO/LVDS26n_235") (pintype "passive"))
    )
    (net (code "135") (name "/MA5") (class "Default")
      (node (ref "U7") (pin "30") (pinfunction "A5_30") (pintype "passive"))
      (node (ref "U8") (pin "234") (pinfunction "IO/LVDS27p_234") (pintype "passive"))
    )
    (net (code "136") (name "/MA6") (class "Default")
      (node (ref "U7") (pin "31") (pinfunction "A6_31") (pintype "passive"))
      (node (ref "U8") (pin "233") (pinfunction "IO/LVDS27n_233") (pintype "passive"))
    )
    (net (code "137") (name "/MA7") (class "Default")
      (node (ref "U7") (pin "32") (pinfunction "A7_32") (pintype "passive"))
      (node (ref "U8") (pin "228") (pinfunction "IO/DPCLK2_228") (pintype "passive"))
    )
    (net (code "138") (name "/MA8") (class "Default")
      (node (ref "U7") (pin "33") (pinfunction "A8_33") (pintype "passive"))
      (node (ref "U8") (pin "227") (pinfunction "IO/VREF2B2_227") (pintype "passive"))
    )
    (net (code "139") (name "/MA9") (class "Default")
      (node (ref "U7") (pin "34") (pinfunction "A9_34") (pintype "passive"))
      (node (ref "U8") (pin "226") (pinfunction "IO/LVDS28p_226") (pintype "passive"))
    )
    (net (code "140") (name "/MA10") (class "Default")
      (node (ref "U7") (pin "22") (pinfunction "A10AP_22") (pintype "passive"))
      (node (ref "U8") (pin "202") (pinfunction "IO/LVDS40n_202") (pintype "passive"))
    )
    (net (code "141") (name "/MA11") (class "Default")
      (node (ref "U7") (pin "35") (pinfunction "A11_35") (pintype "passive"))
      (node (ref "U8") (pin "225") (pinfunction "IO/LVDS28n_225") (pintype "passive"))
    )
    (net (code "142") (name "/MA12") (class "Default")
      (node (ref "U7") (pin "36") (pinfunction "A12_36") (pintype "passive"))
      (node (ref "U8") (pin "224") (pinfunction "IO/LVDS29p_224") (pintype "passive"))
    )
    (net (code "143") (name "/MBA0") (class "Default")
      (node (ref "U7") (pin "20") (pinfunction "BA0_20") (pintype "passive"))
      (node (ref "U8") (pin "200") (pinfunction "IO/LVDS41n_200") (pintype "passive"))
    )
    (net (code "144") (name "/MBA1") (class "Default")
      (node (ref "U7") (pin "21") (pinfunction "BA1_21") (pintype "passive"))
      (node (ref "U8") (pin "201") (pinfunction "IO/LVDS41p_201") (pintype "passive"))
    )
    (net (code "145") (name "/MCAS") (class "Default")
      (node (ref "U7") (pin "17") (pinfunction "CAS#_17") (pintype "passive"))
      (node (ref "U8") (pin "195") (pinfunction "IO_195") (pintype "passive"))
    )
    (net (code "146") (name "/MCKE") (class "Default")
      (node (ref "U7") (pin "37") (pinfunction "CKE_37") (pintype "passive"))
      (node (ref "U8") (pin "39") (pinfunction "IO/PLL1_OUTn_39") (pintype "passive"))
    )
    (net (code "147") (name "/MCLK") (class "Default")
      (node (ref "R13") (pin "2") (pinfunction "2_2") (pintype "passive"))
      (node (ref "U7") (pin "38") (pinfunction "CLK_38") (pintype "passive"))
    )
    (net (code "148") (name "/MCS") (class "Default")
      (node (ref "U7") (pin "19") (pinfunction "CS#_19") (pintype "passive"))
      (node (ref "U8") (pin "197") (pinfunction "IO/LVDS46p_197") (pintype "passive"))
    )
    (net (code "149") (name "/MD0") (class "Default")
      (node (ref "U7") (pin "2") (pinfunction "DQ0_2") (pintype "passive"))
      (node (ref "U8") (pin "181") (pinfunction "IO/LVDS50n_181") (pintype "passive"))
    )
    (net (code "150") (name "/MD1") (class "Default")
      (node (ref "U7") (pin "4") (pinfunction "DQ1_4") (pintype "passive"))
      (node (ref "U8") (pin "182") (pinfunction "IO/LVDS50p_182") (pintype "passive"))
    )
    (net (code "151") (name "/MD2") (class "Default")
      (node (ref "U7") (pin "5") (pinfunction "DQ2_5") (pintype "passive"))
      (node (ref "U8") (pin "183") (pinfunction "IO/LVDS49n_183") (pintype "passive"))
    )
    (net (code "152") (name "/MD3") (class "Default")
      (node (ref "U7") (pin "7") (pinfunction "DQ3_7") (pintype "passive"))
      (node (ref "U8") (pin "184") (pinfunction "IO/LVDS49p_184") (pintype "passive"))
    )
    (net (code "153") (name "/MD4") (class "Default")
      (node (ref "U7") (pin "8") (pinfunction "DQ4_8") (pintype "passive"))
      (node (ref "U8") (pin "185") (pinfunction "IO/LVDS48n_185") (pintype "passive"))
    )
    (net (code "154") (name "/MD5") (class "Default")
      (node (ref "U7") (pin "10") (pinfunction "DQ5_10") (pintype "passive"))
      (node (ref "U8") (pin "186") (pinfunction "IO/LVDS48p_186") (pintype "passive"))
    )
    (net (code "155") (name "/MD6") (class "Default")
      (node (ref "U7") (pin "11") (pinfunction "DQ6_11") (pintype "passive"))
      (node (ref "U8") (pin "187") (pinfunction "IO/LVDS47n_187") (pintype "passive"))
    )
    (net (code "156") (name "/MD7") (class "Default")
      (node (ref "U7") (pin "13") (pinfunction "DQ7_13") (pintype "passive"))
      (node (ref "U8") (pin "188") (pinfunction "IO/LVDS47p_188") (pintype "passive"))
    )
    (net (code "157") (name "/MD8") (class "Default")
      (node (ref "U7") (pin "42") (pinfunction "DQ8_42") (pintype "passive"))
      (node (ref "U8") (pin "222") (pinfunction "IO/LVDS30p_222") (pintype "passive"))
    )
    (net (code "158") (name "/MD9") (class "Default")
      (node (ref "U7") (pin "44") (pinfunction "DQ9_44") (pintype "passive"))
      (node (ref "U8") (pin "219") (pinfunction "IO/LVDS31p_219") (pintype "passive"))
    )
    (net (code "159") (name "/MD10") (class "Default")
      (node (ref "U7") (pin "45") (pinfunction "DQ10_45") (pintype "passive"))
      (node (ref "U8") (pin "218") (pinfunction "IO/LVDS31n_218") (pintype "passive"))
    )
    (net (code "160") (name "/MD11") (class "Default")
      (node (ref "U7") (pin "47") (pinfunction "DQ11_47") (pintype "passive"))
      (node (ref "U8") (pin "217") (pinfunction "IO/LVDS32p_217") (pintype "passive"))
    )
    (net (code "161") (name "/MD12") (class "Default")
      (node (ref "U7") (pin "48") (pinfunction "DQ12_48") (pintype "passive"))
      (node (ref "U8") (pin "216") (pinfunction "IO/LVDS32n_216") (pintype "passive"))
    )
    (net (code "162") (name "/MD13") (class "Default")
      (node (ref "U7") (pin "50") (pinfunction "DQ13_50") (pintype "passive"))
      (node (ref "U8") (pin "215") (pinfunction "IO/LVDS33p_215") (pintype "passive"))
    )
    (net (code "163") (name "/MD14") (class "Default")
      (node (ref "U7") (pin "51") (pinfunction "DQ14_51") (pintype "passive"))
      (node (ref "U8") (pin "214") (pinfunction "IO/LVDS33n_214") (pintype "passive"))
    )
    (net (code "164") (name "/MD15") (class "Default")
      (node (ref "U7") (pin "53") (pinfunction "DQ15_53") (pintype "passive"))
      (node (ref "U8") (pin "213") (pinfunction "IO/LVDS34p_213") (pintype "passive"))
    )
    (net (code "166") (name "/MLDQ") (class "Default")
      (node (ref "U7") (pin "15") (pinfunction "LDQM_15") (pintype "passive"))
      (node (ref "U8") (pin "193") (pinfunction "IO/DPCLK3_193") (pintype "passive"))
    )
    (net (code "167") (name "/MRAS") (class "Default")
      (node (ref "U7") (pin "18") (pinfunction "RAS#_18") (pintype "passive"))
      (node (ref "U8") (pin "196") (pinfunction "IO/LVDS46n_196") (pintype "passive"))
    )
    (net (code "168") (name "/MUDQ") (class "Default")
      (node (ref "U7") (pin "39") (pinfunction "DQM_39") (pintype "passive"))
      (node (ref "U8") (pin "223") (pinfunction "IO/LVDS29n_223") (pintype "passive"))
    )
    (net (code "169") (name "/MWE") (class "Default")
      (node (ref "U7") (pin "16") (pinfunction "WE#_16") (pintype "passive"))
      (node (ref "U8") (pin "194") (pinfunction "IO/VREF0B2_194") (pintype "passive"))
    )
    (net (code "170") (name "/PWRLED") (class "Default")
      (node (ref "H4") (pin "47") (pinfunction "47_47") (pintype "passive"))
      (node (ref "U8") (pin "240") (pinfunction "IO/LVDS24p/DEV_CLRn_240") (pintype "passive"))
    )
    (net (code "176") (name "/SL0") (class "Default")
      (node (ref "H2") (pin "22") (pinfunction "22_22") (pintype "passive"))
      (node (ref "U8") (pin "105") (pinfunction "IO/LVDS80n_105") (pintype "passive"))
    )
    (net (code "177") (name "/SL1") (class "Default")
      (node (ref "H2") (pin "21") (pinfunction "21_21") (pintype "passive"))
      (node (ref "U8") (pin "106") (pinfunction "IO_106") (pintype "passive"))
    )
    (net (code "178") (name "/SL2") (class "Default")
      (node (ref "H2") (pin "24") (pinfunction "24_24") (pintype "passive"))
      (node (ref "U8") (pin "107") (pinfunction "IO/VREF0B4_107") (pintype "passive"))
    )
    (net (code "179") (name "/SL3") (class "Default")
      (node (ref "H2") (pin "23") (pinfunction "23_23") (pintype "passive"))
      (node (ref "U8") (pin "108") (pinfunction "IO/DPCLK6_108") (pintype "passive"))
    )
    (net (code "180") (name "/SL4") (class "Default")
      (node (ref "H2") (pin "26") (pinfunction "26_26") (pintype "passive"))
      (node (ref "U8") (pin "113") (pinfunction "IO/LVDS79p_113") (pintype "passive"))
    )
    (net (code "181") (name "/SL5") (class "Default")
      (node (ref "H2") (pin "25") (pinfunction "25_25") (pintype "passive"))
      (node (ref "U8") (pin "114") (pinfunction "IO/LVDS79n_114") (pintype "passive"))
    )
    (net (code "184") (name "/SR0") (class "Default")
      (node (ref "H2") (pin "28") (pinfunction "28_28") (pintype "passive"))
      (node (ref "U8") (pin "115") (pinfunction "IO/LVDS78p_115") (pintype "passive"))
    )
    (net (code "185") (name "/SR1") (class "Default")
      (node (ref "H2") (pin "27") (pinfunction "27_27") (pintype "passive"))
      (node (ref "U8") (pin "116") (pinfunction "IO/LVDS78n_116") (pintype "passive"))
    )
    (net (code "186") (name "/SR2") (class "Default")
      (node (ref "H2") (pin "30") (pinfunction "30_30") (pintype "passive"))
      (node (ref "U8") (pin "117") (pinfunction "IO/LVDS77p_117") (pintype "passive"))
    )
    (net (code "187") (name "/SR3") (class "Default")
      (node (ref "H2") (pin "29") (pinfunction "29_29") (pintype "passive"))
      (node (ref "U8") (pin "118") (pinfunction "IO/LVDS77n_118") (pintype "passive"))
    )
    (net (code "188") (name "/SR4") (class "Default")
      (node (ref "H2") (pin "32") (pinfunction "32_32") (pintype "passive"))
      (node (ref "U8") (pin "119") (pinfunction "IO/LVDS76p_119") (pintype "passive"))
    )
    (net (code "189") (name "/SR5") (class "Default")
      (node (ref "H2") (pin "31") (pinfunction "31_31") (pintype "passive"))
      (node (ref "U8") (pin "120") (pinfunction "IO/LVDS76n_120") (pintype "passive"))
    )
    (net (code "192") (name "/USBN1") (class "Default")
      (node (ref "H4") (pin "44") (pinfunction "44_44") (pintype "passive"))
      (node (ref "U8") (pin "236") (pinfunction "IO/LVDS26p_236") (pintype "passive"))
    )
    (net (code "193") (name "/USBP1") (class "Default")
      (node (ref "H4") (pin "43") (pinfunction "43_43") (pintype "passive"))
      (node (ref "U8") (pin "237") (pinfunction "IO/LVDS25n_237") (pintype "passive"))
    )
    (net (code "194") (name "/VB0") (class "Default")
      (node (ref "H2") (pin "1") (pinfunction "1_1") (pintype "passive"))
      (node (ref "U8") (pin "77") (pinfunction "IO/LVDS97p_77") (pintype "passive"))
    )
    (net (code "195") (name "/VB1") (class "Default")
      (node (ref "H2") (pin "2") (pinfunction "2_2") (pintype "passive"))
      (node (ref "U8") (pin "78") (pinfunction "IO/LVDS97n_78") (pintype "passive"))
    )
    (net (code "196") (name "/VB2") (class "Default")
      (node (ref "H2") (pin "3") (pinfunction "3_3") (pintype "passive"))
      (node (ref "U8") (pin "79") (pinfunction "IO/LVDS96p_79") (pintype "passive"))
    )
    (net (code "197") (name "/VB3") (class "Default")
      (node (ref "H2") (pin "4") (pinfunction "4_4") (pintype "passive"))
      (node (ref "U8") (pin "82") (pinfunction "IO/LVDS95p_82") (pintype "passive"))
    )
    (net (code "198") (name "/VB4") (class "Default")
      (node (ref "H2") (pin "5") (pinfunction "5_5") (pintype "passive"))
      (node (ref "U8") (pin "83") (pinfunction "IO/LVDS95n_83") (pintype "passive"))
    )
    (net (code "199") (name "/VB5") (class "Default")
      (node (ref "H2") (pin "6") (pinfunction "6_6") (pintype "passive"))
      (node (ref "U8") (pin "84") (pinfunction "IO/LVDS94p_84") (pintype "passive"))
    )
    (net (code "200") (name "/VG0") (class "Default")
      (node (ref "H2") (pin "7") (pinfunction "7_7") (pintype "passive"))
      (node (ref "U8") (pin "85") (pinfunction "IO/LVDS94n_85") (pintype "passive"))
    )
    (net (code "201") (name "/VG1") (class "Default")
      (node (ref "H2") (pin "8") (pinfunction "8_8") (pintype "passive"))
      (node (ref "U8") (pin "86") (pinfunction "IO/LVDS93p_86") (pintype "passive"))
    )
    (net (code "202") (name "/VG2") (class "Default")
      (node (ref "H2") (pin "9") (pinfunction "9_9") (pintype "passive"))
      (node (ref "U8") (pin "87") (pinfunction "IO/LVDS93n_87") (pintype "passive"))
    )
    (net (code "203") (name "/VG3") (class "Default")
      (node (ref "H2") (pin "10") (pinfunction "10_10") (pintype "passive"))
      (node (ref "U8") (pin "88") (pinfunction "IO/LVDS92p_88") (pintype "passive"))
    )
    (net (code "204") (name "/VG4") (class "Default")
      (node (ref "H2") (pin "11") (pinfunction "11_11") (pintype "passive"))
      (node (ref "U8") (pin "93") (pinfunction "IO/VREF1B4_93") (pintype "passive"))
    )
    (net (code "205") (name "/VG5") (class "Default")
      (node (ref "H2") (pin "12") (pinfunction "12_12") (pintype "passive"))
      (node (ref "U8") (pin "94") (pinfunction "IO/LVDS87p_94") (pintype "passive"))
    )
    (net (code "206") (name "/VR0") (class "Default")
      (node (ref "H2") (pin "13") (pinfunction "13_13") (pintype "passive"))
      (node (ref "U8") (pin "95") (pinfunction "IO/LVDS87n_95") (pintype "passive"))
    )
    (net (code "207") (name "/VR1") (class "Default")
      (node (ref "H2") (pin "14") (pinfunction "14_14") (pintype "passive"))
      (node (ref "U8") (pin "98") (pinfunction "IO/LVDS86p_98") (pintype "passive"))
    )
    (net (code "208") (name "/VR2") (class "Default")
      (node (ref "H2") (pin "15") (pinfunction "15_15") (pintype "passive"))
      (node (ref "U8") (pin "99") (pinfunction "IO/LVDS86n_99") (pintype "passive"))
    )
    (net (code "209") (name "/VR3") (class "Default")
      (node (ref "H2") (pin "16") (pinfunction "16_16") (pintype "passive"))
      (node (ref "U8") (pin "100") (pinfunction "IO/LVDS85p_100") (pintype "passive"))
    )
    (net (code "210") (name "/VR4") (class "Default")
      (node (ref "H2") (pin "17") (pinfunction "17_17") (pintype "passive"))
      (node (ref "U8") (pin "101") (pinfunction "IO/LVDS85n_101") (pintype "passive"))
    )
    (net (code "211") (name "/VR5") (class "Default")
      (node (ref "H2") (pin "18") (pinfunction "18_18") (pintype "passive"))
      (node (ref "U8") (pin "104") (pinfunction "IO/LVDS80p_104") (pintype "passive"))
    )
    (net (code "214") (name "<NO NET>") (class "Default")
      (node (ref "C1") (pin "1") (pinfunction "1_1") (pintype "passive"))
      (node (ref "C10") (pin "1") (pinfunction "1_1") (pintype "passive"))
      (node (ref "C11") (pin "1") (pinfunction "1_1") (pintype "passive"))
      (node (ref "C12") (pin "1") (pinfunction "1_1") (pintype "passive"))
      (node (ref "C13") (pin "1") (pinfunction "1_1") (pintype "passive"))
      (node (ref "C14") (pin "1") (pinfunction "1_1") (pintype "passive"))
      (node (ref "C15") (pin "1") (pinfunction "1_1") (pintype "passive"))
      (node (ref "C16") (pin "1") (pinfunction "1_1") (pintype "passive"))
      (node (ref "C17") (pin "1") (pinfunction "1_1") (pintype "passive"))
      (node (ref "C18") (pin "1") (pinfunction "1_1") (pintype "passive"))
      (node (ref "C19") (pin "1") (pinfunction "1_1") (pintype "passive"))
      (node (ref "C20") (pin "1") (pinfunction "1_1") (pintype "passive"))
      (node (ref "C21") (pin "1") (pinfunction "1_1") (pintype "passive"))
      (node (ref "C23") (pin "2") (pinfunction "2_2") (pintype "passive"))
      (node (ref "C3") (pin "1") (pinfunction "1_1") (pintype "passive"))
      (node (ref "C4") (pin "1") (pinfunction "1_1") (pintype "passive"))
      (node (ref "C6") (pin "1") (pinfunction "1_1") (pintype "passive"))
      (node (ref "C7") (pin "1") (pinfunction "1_1") (pintype "passive"))
      (node (ref "C8") (pin "1") (pinfunction "1_1") (pintype "passive"))
      (node (ref "C9") (pin "1") (pinfunction "1_1") (pintype "passive"))
      (node (ref "R5") (pin "2") (pinfunction "2_2") (pintype "passive"))
      (node (ref "R6") (pin "2") (pinfunction "2_2") (pintype "passive"))
      (node (ref "R7") (pin "2") (pinfunction "2_2") (pintype "passive"))
      (node (ref "R8") (pin "2") (pinfunction "2_2") (pintype "passive"))
      (node (ref "U2") (pin "7") (pinfunction "EH_7") (pintype "passive"))
      (node (ref "U2") (pin "A12") (pinfunction "GND_A12") (pintype "passive"))
      (node (ref "U2") (pin "B12") (pinfunction "GND_B12") (pintype "passive"))
    )
    (net (code "215") (name "GND") (class "Default")
      (node (ref "C2") (pin "1") (pinfunction "1_1") (pintype "passive"))
      (node (ref "C22") (pin "2") (pinfunction "2_2") (pintype "passive"))
      (node (ref "C5") (pin "1") (pinfunction "1_1") (pintype "passive"))
      (node (ref "H1") (pin "10") (pinfunction "10_10") (pintype "passive"))
      (node (ref "H1") (pin "2") (pinfunction "2_2") (pintype "passive"))
      (node (ref "H2") (pin "19") (pinfunction "19_19") (pintype "passive"))
      (node (ref "H2") (pin "20") (pinfunction "20_20") (pintype "passive"))
      (node (ref "H3") (pin "46") (pinfunction "46_46") (pintype "passive"))
      (node (ref "H4") (pin "45") (pinfunction "45_45") (pintype "passive"))
      (node (ref "H4") (pin "46") (pinfunction "46_46") (pintype "passive"))
      (node (ref "RN2") (pin "5") (pinfunction "5_5") (pintype "passive"))
      (node (ref "U1") (pin "2") (pinfunction "GND_2") (pintype "passive"))
      (node (ref "U4") (pin "4") (pinfunction "GND_4") (pintype "passive"))
      (node (ref "U5") (pin "1") (pinfunction "GND_1") (pintype "passive"))
      (node (ref "U6") (pin "1") (pinfunction "GND_1") (pintype "passive"))
      (node (ref "U7") (pin "12") (pinfunction "VSSQ_12") (pintype "passive"))
      (node (ref "U7") (pin "28") (pinfunction "VSS_28") (pintype "passive"))
      (node (ref "U7") (pin "41") (pinfunction "VSS_41") (pintype "passive"))
      (node (ref "U7") (pin "46") (pinfunction "VSSQ_46") (pintype "passive"))
      (node (ref "U7") (pin "52") (pinfunction "VSSQ_52") (pintype "passive"))
      (node (ref "U7") (pin "54") (pinfunction "VSS_54") (pintype "passive"))
      (node (ref "U7") (pin "6") (pinfunction "VSSQ_6") (pintype "passive"))
      (node (ref "U8") (pin "10") (pinfunction "GND_10") (pintype "passive"))
      (node (ref "U8") (pin "102") (pinfunction "GND_102") (pintype "passive"))
      (node (ref "U8") (pin "109") (pinfunction "GND_109") (pintype "passive"))
      (node (ref "U8") (pin "111") (pinfunction "GND_111") (pintype "passive"))
      (node (ref "U8") (pin "129") (pinfunction "GND_129") (pintype "passive"))
      (node (ref "U8") (pin "142") (pinfunction "GND_142") (pintype "passive"))
      (node (ref "U8") (pin "147") (pinfunction "TCK/TCK_147") (pintype "passive"))
      (node (ref "U8") (pin "150") (pinfunction "GNDG_PLL2_150") (pintype "passive"))
      (node (ref "U8") (pin "151") (pinfunction "GNDA_PLL2_151") (pintype "passive"))
      (node (ref "U8") (pin "171") (pinfunction "GND_171") (pintype "passive"))
      (node (ref "U8") (pin "190") (pinfunction "GND_190") (pintype "passive"))
      (node (ref "U8") (pin "192") (pinfunction "GND_192") (pintype "passive"))
      (node (ref "U8") (pin "199") (pinfunction "GND_199") (pintype "passive"))
      (node (ref "U8") (pin "205") (pinfunction "GND_205") (pintype "passive"))
      (node (ref "U8") (pin "210") (pinfunction "GND_210") (pintype "passive"))
      (node (ref "U8") (pin "212") (pinfunction "GND_212") (pintype "passive"))
      (node (ref "U8") (pin "221") (pinfunction "GND_221") (pintype "passive"))
      (node (ref "U8") (pin "230") (pinfunction "GND_230") (pintype "passive"))
      (node (ref "U8") (pin "232") (pinfunction "GND_232") (pintype "passive"))
      (node (ref "U8") (pin "30") (pinfunction "GNDA_PLL1_30") (pintype "passive"))
      (node (ref "U8") (pin "31") (pinfunction "GNDG_PLL1_31") (pintype "passive"))
      (node (ref "U8") (pin "34") (pinfunction "MSEL0/MSEL0_34") (pintype "passive"))
      (node (ref "U8") (pin "35") (pinfunction "MSEL1/MSEL1_35") (pintype "passive"))
      (node (ref "U8") (pin "40") (pinfunction "GND_40") (pintype "passive"))
      (node (ref "U8") (pin "52") (pinfunction "GND_52") (pintype "passive"))
      (node (ref "U8") (pin "69") (pinfunction "GND_69") (pintype "passive"))
      (node (ref "U8") (pin "71") (pinfunction "GND_71") (pintype "passive"))
      (node (ref "U8") (pin "80") (pinfunction "GND_80") (pintype "passive"))
      (node (ref "U8") (pin "89") (pinfunction "GND_89") (pintype "passive"))
      (node (ref "U8") (pin "91") (pinfunction "GND_91") (pintype "passive"))
      (node (ref "U8") (pin "96") (pinfunction "GND_96") (pintype "passive"))
    )
    (net (code "216") (name "Net-(LED1-C)") (class "Default")
      (node (ref "LED1") (pin "1") (pinfunction "C_1") (pintype "passive"))
      (node (ref "R5") (pin "1") (pinfunction "1_1") (pintype "passive"))
    )
    (net (code "217") (name "Net-(LED2-C)") (class "Default")
      (node (ref "LED2") (pin "1") (pinfunction "C_1") (pintype "passive"))
      (node (ref "R6") (pin "1") (pinfunction "1_1") (pintype "passive"))
    )
    (net (code "218") (name "Net-(LED3-C)") (class "Default")
      (node (ref "LED3") (pin "1") (pinfunction "C_1") (pintype "passive"))
      (node (ref "R7") (pin "1") (pinfunction "1_1") (pintype "passive"))
    )
    (net (code "219") (name "Net-(LED4-C)") (class "Default")
      (node (ref "LED4") (pin "1") (pinfunction "C_1") (pintype "passive"))
      (node (ref "R8") (pin "1") (pinfunction "1_1") (pintype "passive"))
    )
    (net (code "220") (name "Net-(U1-A1)") (class "Default")
      (node (ref "R3") (pin "2") (pinfunction "2_2") (pintype "passive"))
      (node (ref "R4") (pin "2") (pinfunction "2_2") (pintype "passive"))
      (node (ref "U1") (pin "1") (pinfunction "A1_1") (pintype "passive"))
      (node (ref "U1") (pin "4") (pinfunction "Y2_4") (pintype "passive"))
    )
    (net (code "221") (name "Net-(U1-A2)") (class "Default")
      (node (ref "C2") (pin "2") (pinfunction "2_2") (pintype "passive"))
      (node (ref "R3") (pin "1") (pinfunction "1_1") (pintype "passive"))
      (node (ref "U1") (pin "3") (pinfunction "A2_3") (pintype "passive"))
      (node (ref "U3") (pin "1") (pinfunction "OSC1_1") (pintype "passive"))
    )
    (net (code "222") (name "Net-(U1-Y1)") (class "Default")
      (node (ref "R10") (pin "1") (pinfunction "1_1") (pintype "passive"))
      (node (ref "R9") (pin "1") (pinfunction "1_1") (pintype "passive"))
      (node (ref "U1") (pin "6") (pinfunction "Y1_6") (pintype "passive"))
    )
    (net (code "223") (name "Net-(U3-OSC2)") (class "Default")
      (node (ref "C5") (pin "2") (pinfunction "2_2") (pintype "passive"))
      (node (ref "R4") (pin "1") (pinfunction "1_1") (pintype "passive"))
      (node (ref "U3") (pin "2") (pinfunction "OSC2_2") (pintype "passive"))
    )
    (net (code "224") (name "Net-(U8B-IO{slash}PLL1_OUTp)") (class "Default")
      (node (ref "R13") (pin "1") (pinfunction "1_1") (pintype "passive"))
      (node (ref "U8") (pin "38") (pinfunction "IO/PLL1_OUTp_38") (pintype "passive"))
    )
    (net (code "225") (name "Net-(U8C-VCCA_PLL1)") (class "Default")
      (node (ref "C22") (pin "1") (pinfunction "1_1") (pintype "passive"))
      (node (ref "R11") (pin "1") (pinfunction "1_1") (pintype "passive"))
      (node (ref "U8") (pin "27") (pinfunction "VCCA_PLL1_27") (pintype "passive"))
    )
    (net (code "226") (name "Net-(U8C-VCCA_PLL2)") (class "Default")
      (node (ref "C23") (pin "1") (pinfunction "1_1") (pintype "passive"))
      (node (ref "R12") (pin "1") (pinfunction "1_1") (pintype "passive"))
      (node (ref "U8") (pin "154") (pinfunction "VCCA_PLL2_154") (pintype "passive"))
    )
    (net (code "227") (name "VCC5") (class "Default")
      (node (ref "C7") (pin "2") (pinfunction "2_2") (pintype "passive"))
      (node (ref "H3") (pin "47") (pinfunction "47_47") (pintype "passive"))
      (node (ref "H3") (pin "48") (pinfunction "48_48") (pintype "passive"))
      (node (ref "LED2") (pin "2") (pinfunction "A_2") (pintype "passive"))
      (node (ref "U2") (pin "A9") (pinfunction "VBUS_A9") (pintype "passive"))
      (node (ref "U2") (pin "B9") (pinfunction "VBUS_B9") (pintype "passive"))
      (node (ref "U5") (pin "3") (pinfunction "VIN_3") (pintype "passive"))
      (node (ref "U6") (pin "3") (pinfunction "VIN_3") (pintype "passive"))
    )
    (net (code "228") (name "VCC15") (class "Default")
      (node (ref "C11") (pin "2") (pinfunction "2_2") (pintype "passive"))
      (node (ref "C14") (pin "2") (pinfunction "2_2") (pintype "passive"))
      (node (ref "C17") (pin "2") (pinfunction "2_2") (pintype "passive"))
      (node (ref "LED4") (pin "2") (pinfunction "A_2") (pintype "passive"))
      (node (ref "R11") (pin "2") (pinfunction "2_2") (pintype "passive"))
      (node (ref "R12") (pin "2") (pinfunction "2_2") (pintype "passive"))
      (node (ref "U5") (pin "2") (pinfunction "VOUT_2") (pintype "passive"))
      (node (ref "U5") (pin "4") (pinfunction "VOUT_4") (pintype "passive"))
      (node (ref "U8") (pin "103") (pinfunction "VCCINT_103") (pintype "passive"))
      (node (ref "U8") (pin "110") (pinfunction "VCCINT_110") (pintype "passive"))
      (node (ref "U8") (pin "191") (pinfunction "VCCINT_191") (pintype "passive"))
      (node (ref "U8") (pin "198") (pinfunction "VCCINT_198") (pintype "passive"))
      (node (ref "U8") (pin "204") (pinfunction "VCCINT_204") (pintype "passive"))
      (node (ref "U8") (pin "211") (pinfunction "VCCINT_211") (pintype "passive"))
      (node (ref "U8") (pin "220") (pinfunction "VCCINT_220") (pintype "passive"))
      (node (ref "U8") (pin "229") (pinfunction "VCCINT_229") (pintype "passive"))
      (node (ref "U8") (pin "72") (pinfunction "VCCINT_72") (pintype "passive"))
      (node (ref "U8") (pin "81") (pinfunction "VCCINT_81") (pintype "passive"))
      (node (ref "U8") (pin "90") (pinfunction "VCCINT_90") (pintype "passive"))
      (node (ref "U8") (pin "97") (pinfunction "VCCINT_97") (pintype "passive"))
    )
    (net (code "229") (name "VCC33") (class "Default")
      (node (ref "C1") (pin "2") (pinfunction "2_2") (pintype "passive"))
      (node (ref "C10") (pin "2") (pinfunction "2_2") (pintype "passive"))
      (node (ref "C12") (pin "2") (pinfunction "2_2") (pintype "passive"))
      (node (ref "C13") (pin "2") (pinfunction "2_2") (pintype "passive"))
      (node (ref "C15") (pin "2") (pinfunction "2_2") (pintype "passive"))
      (node (ref "C16") (pin "2") (pinfunction "2_2") (pintype "passive"))
      (node (ref "C18") (pin "2") (pinfunction "2_2") (pintype "passive"))
      (node (ref "C19") (pin "2") (pinfunction "2_2") (pintype "passive"))
      (node (ref "C20") (pin "2") (pinfunction "2_2") (pintype "passive"))
      (node (ref "C21") (pin "2") (pinfunction "2_2") (pintype "passive"))
      (node (ref "C3") (pin "2") (pinfunction "2_2") (pintype "passive"))
      (node (ref "C4") (pin "2") (pinfunction "2_2") (pintype "passive"))
      (node (ref "C6") (pin "2") (pinfunction "2_2") (pintype "passive"))
      (node (ref "C8") (pin "2") (pinfunction "2_2") (pintype "passive"))
      (node (ref "C9") (pin "2") (pinfunction "2_2") (pintype "passive"))
      (node (ref "H1") (pin "4") (pinfunction "4_4") (pintype "passive"))
      (node (ref "H4") (pin "48") (pinfunction "48_48") (pintype "passive"))
      (node (ref "LED3") (pin "2") (pinfunction "A_2") (pintype "passive"))
      (node (ref "RN2") (pin "6") (pinfunction "6_6") (pintype "passive"))
      (node (ref "RN2") (pin "7") (pinfunction "7_7") (pintype "passive"))
      (node (ref "RN2") (pin "8") (pinfunction "8_8") (pintype "passive"))
      (node (ref "U1") (pin "5") (pinfunction "VCC_5") (pintype "passive"))
      (node (ref "U4") (pin "3") (pinfunction "VCC_3") (pintype "passive"))
      (node (ref "U4") (pin "7") (pinfunction "VCC_7") (pintype "passive"))
      (node (ref "U4") (pin "8") (pinfunction "VCC_8") (pintype "passive"))
      (node (ref "U6") (pin "2") (pinfunction "VOUT_2") (pintype "passive"))
      (node (ref "U6") (pin "4") (pinfunction "VOUT_4") (pintype "passive"))
      (node (ref "U7") (pin "1") (pinfunction "VDD_1") (pintype "passive"))
      (node (ref "U7") (pin "14") (pinfunction "VDD_14") (pintype "passive"))
      (node (ref "U7") (pin "27") (pinfunction "VDD_27") (pintype "passive"))
      (node (ref "U7") (pin "3") (pinfunction "VDDQ_3") (pintype "passive"))
      (node (ref "U7") (pin "43") (pinfunction "VDDQ_43") (pintype "passive"))
      (node (ref "U7") (pin "49") (pinfunction "VDDQ_49") (pintype "passive"))
      (node (ref "U7") (pin "9") (pinfunction "VDDQ_9") (pintype "passive"))
      (node (ref "U8") (pin "112") (pinfunction "VCCIO4_112") (pintype "passive"))
      (node (ref "U8") (pin "130") (pinfunction "VCCIO3_130") (pintype "passive"))
      (node (ref "U8") (pin "148") (pinfunction "TMS/TMS_148") (pintype "passive"))
      (node (ref "U8") (pin "155") (pinfunction "TDI/TDI_155") (pintype "passive"))
      (node (ref "U8") (pin "157") (pinfunction "VCCIO3_157") (pintype "passive"))
      (node (ref "U8") (pin "172") (pinfunction "VCCIO3_172") (pintype "passive"))
      (node (ref "U8") (pin "189") (pinfunction "VCCIO2_189") (pintype "passive"))
      (node (ref "U8") (pin "209") (pinfunction "VCCIO2_209") (pintype "passive"))
      (node (ref "U8") (pin "22") (pinfunction "VCCIO1_22") (pintype "passive"))
      (node (ref "U8") (pin "231") (pinfunction "VCCIO2_231") (pintype "passive"))
      (node (ref "U8") (pin "51") (pinfunction "VCCIO1_51") (pintype "passive"))
      (node (ref "U8") (pin "70") (pinfunction "VCCIO4_70") (pintype "passive"))
      (node (ref "U8") (pin "9") (pinfunction "VCCIO1_9") (pintype "passive"))
      (node (ref "U8") (pin "92") (pinfunction "VCCIO4_92") (pintype "passive"))
    )
    (net (code "230") (name "unconnected-(U2-CC1-PadA5)") (class "Default")
      (node (ref "U2") (pin "A5") (pinfunction "CC1_A5") (pintype "passive+no_connect"))
    )
    (net (code "231") (name "unconnected-(U2-CC2-PadB5)") (class "Default")
      (node (ref "U2") (pin "B5") (pinfunction "CC2_B5") (pintype "passive+no_connect"))
    )
    (net (code "232") (name "unconnected-(U7-NC-Pad40)") (class "Default")
      (node (ref "U7") (pin "40") (pinfunction "NC_40") (pintype "passive+no_connect"))
    )
    (net (code "233") (name "unconnected-(U8A-IO{slash}LVDS16n-Pad21)") (class "Default")
      (node (ref "U8") (pin "21") (pinfunction "IO/LVDS16n_21") (pintype "passive+no_connect"))
    )
    (net (code "234") (name "unconnected-(U8A-IO{slash}LVDS16p-Pad20)") (class "Default")
      (node (ref "U8") (pin "20") (pinfunction "IO/LVDS16p_20") (pintype "passive+no_connect"))
    )
    (net (code "235") (name "unconnected-(U8A-IO{slash}LVDS17n-Pad19)") (class "Default")
      (node (ref "U8") (pin "19") (pinfunction "IO/LVDS17n_19") (pintype "passive+no_connect"))
    )
    (net (code "236") (name "unconnected-(U8A-IO{slash}LVDS17p-Pad18)") (class "Default")
      (node (ref "U8") (pin "18") (pinfunction "IO/LVDS17p_18") (pintype "passive+no_connect"))
    )
    (net (code "237") (name "unconnected-(U8A-IO{slash}LVDS18n-Pad17)") (class "Default")
      (node (ref "U8") (pin "17") (pinfunction "IO/LVDS18n_17") (pintype "passive+no_connect"))
    )
    (net (code "238") (name "unconnected-(U8A-IO{slash}LVDS24n{slash}DEV_OE-Pad239)") (class "Default")
      (node (ref "U8") (pin "239") (pinfunction "IO/LVDS24n/DEV_OE_239") (pintype "passive+no_connect"))
    )
    (net (code "239") (name "unconnected-(U8A-IO{slash}LVDS25p-Pad238)") (class "Default")
      (node (ref "U8") (pin "238") (pinfunction "IO/LVDS25p_238") (pintype "passive+no_connect"))
    )
    (net (code "240") (name "unconnected-(U8B-IO{slash}LVDS6p-Pad42)") (class "Default")
      (node (ref "U8") (pin "42") (pinfunction "IO/LVDS6p_42") (pintype "passive+no_connect"))
    )
    (net (code "241") (name "unconnected-(U8B-IO{slash}LVDS7n-Pad41)") (class "Default")
      (node (ref "U8") (pin "41") (pinfunction "IO/LVDS7n_41") (pintype "passive+no_connect"))
    )
    (net (code "242") (name "unconnected-(U8B-IO{slash}VREF1B1-Pad23)") (class "Default")
      (node (ref "U8") (pin "23") (pinfunction "IO/VREF1B1_23") (pintype "passive+no_connect"))
    )
    (net (code "243") (name "unconnected-(U8B-TDO{slash}TDO-Pad149)") (class "Default")
      (node (ref "U8") (pin "149") (pinfunction "TDO/TDO_149") (pintype "passive+no_connect"))
    )
    (net (code "244") (name "unconnected-(U8B-nCEO{slash}nCEO-Pad32)") (class "Default")
      (node (ref "U8") (pin "32") (pinfunction "nCEO/nCEO_32") (pintype "passive+no_connect"))
    )
  )
)
